# Eddy_Backplane.net
KiCad netlist of a schematic drawn in EAGLE
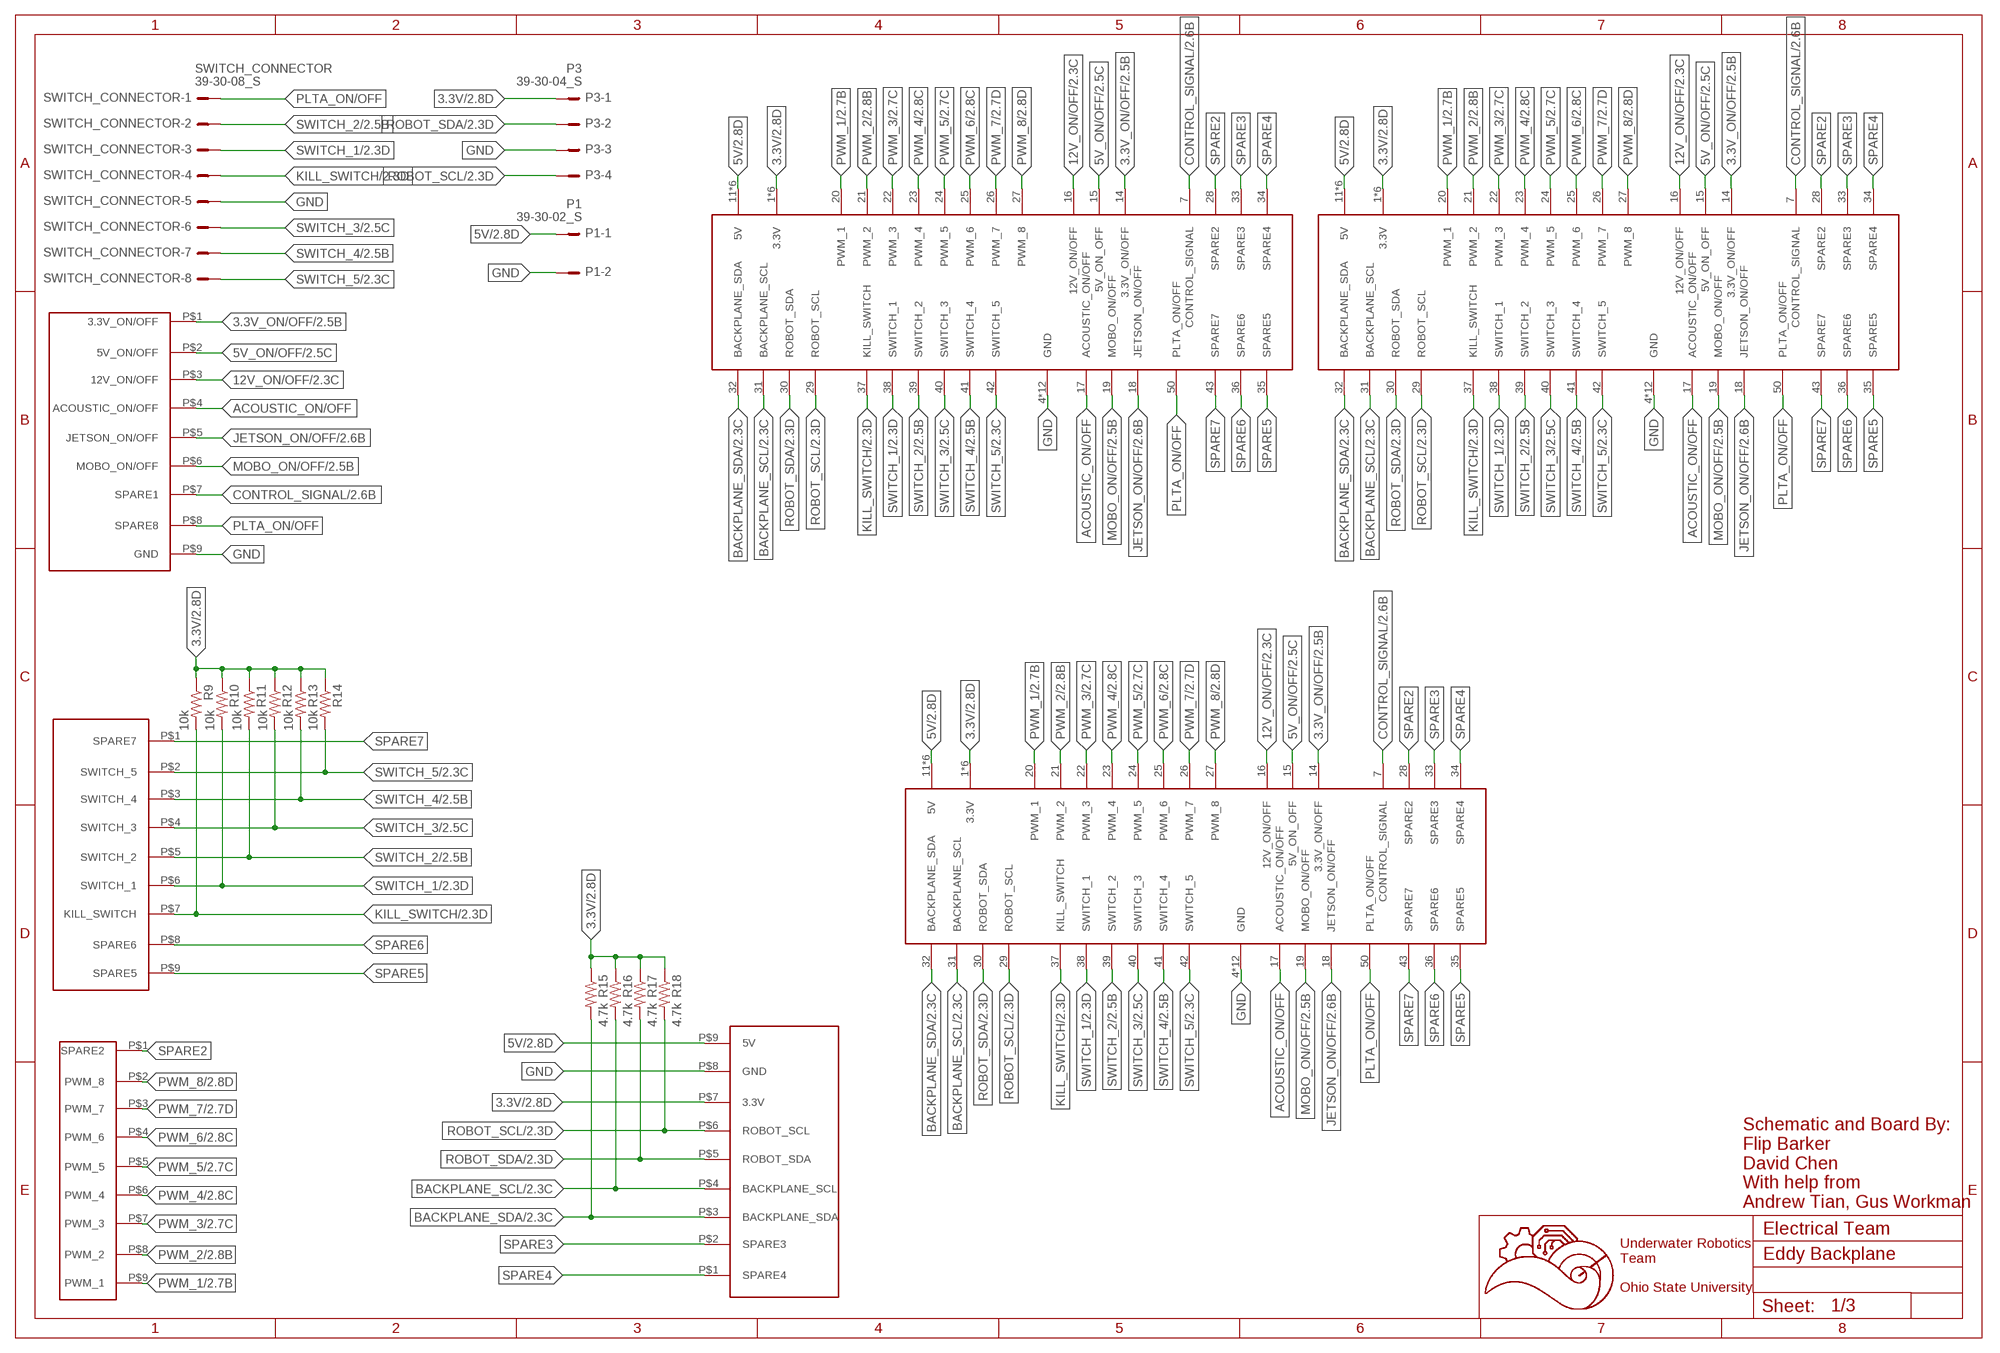
[diagram p0: schematic, sheet 1]
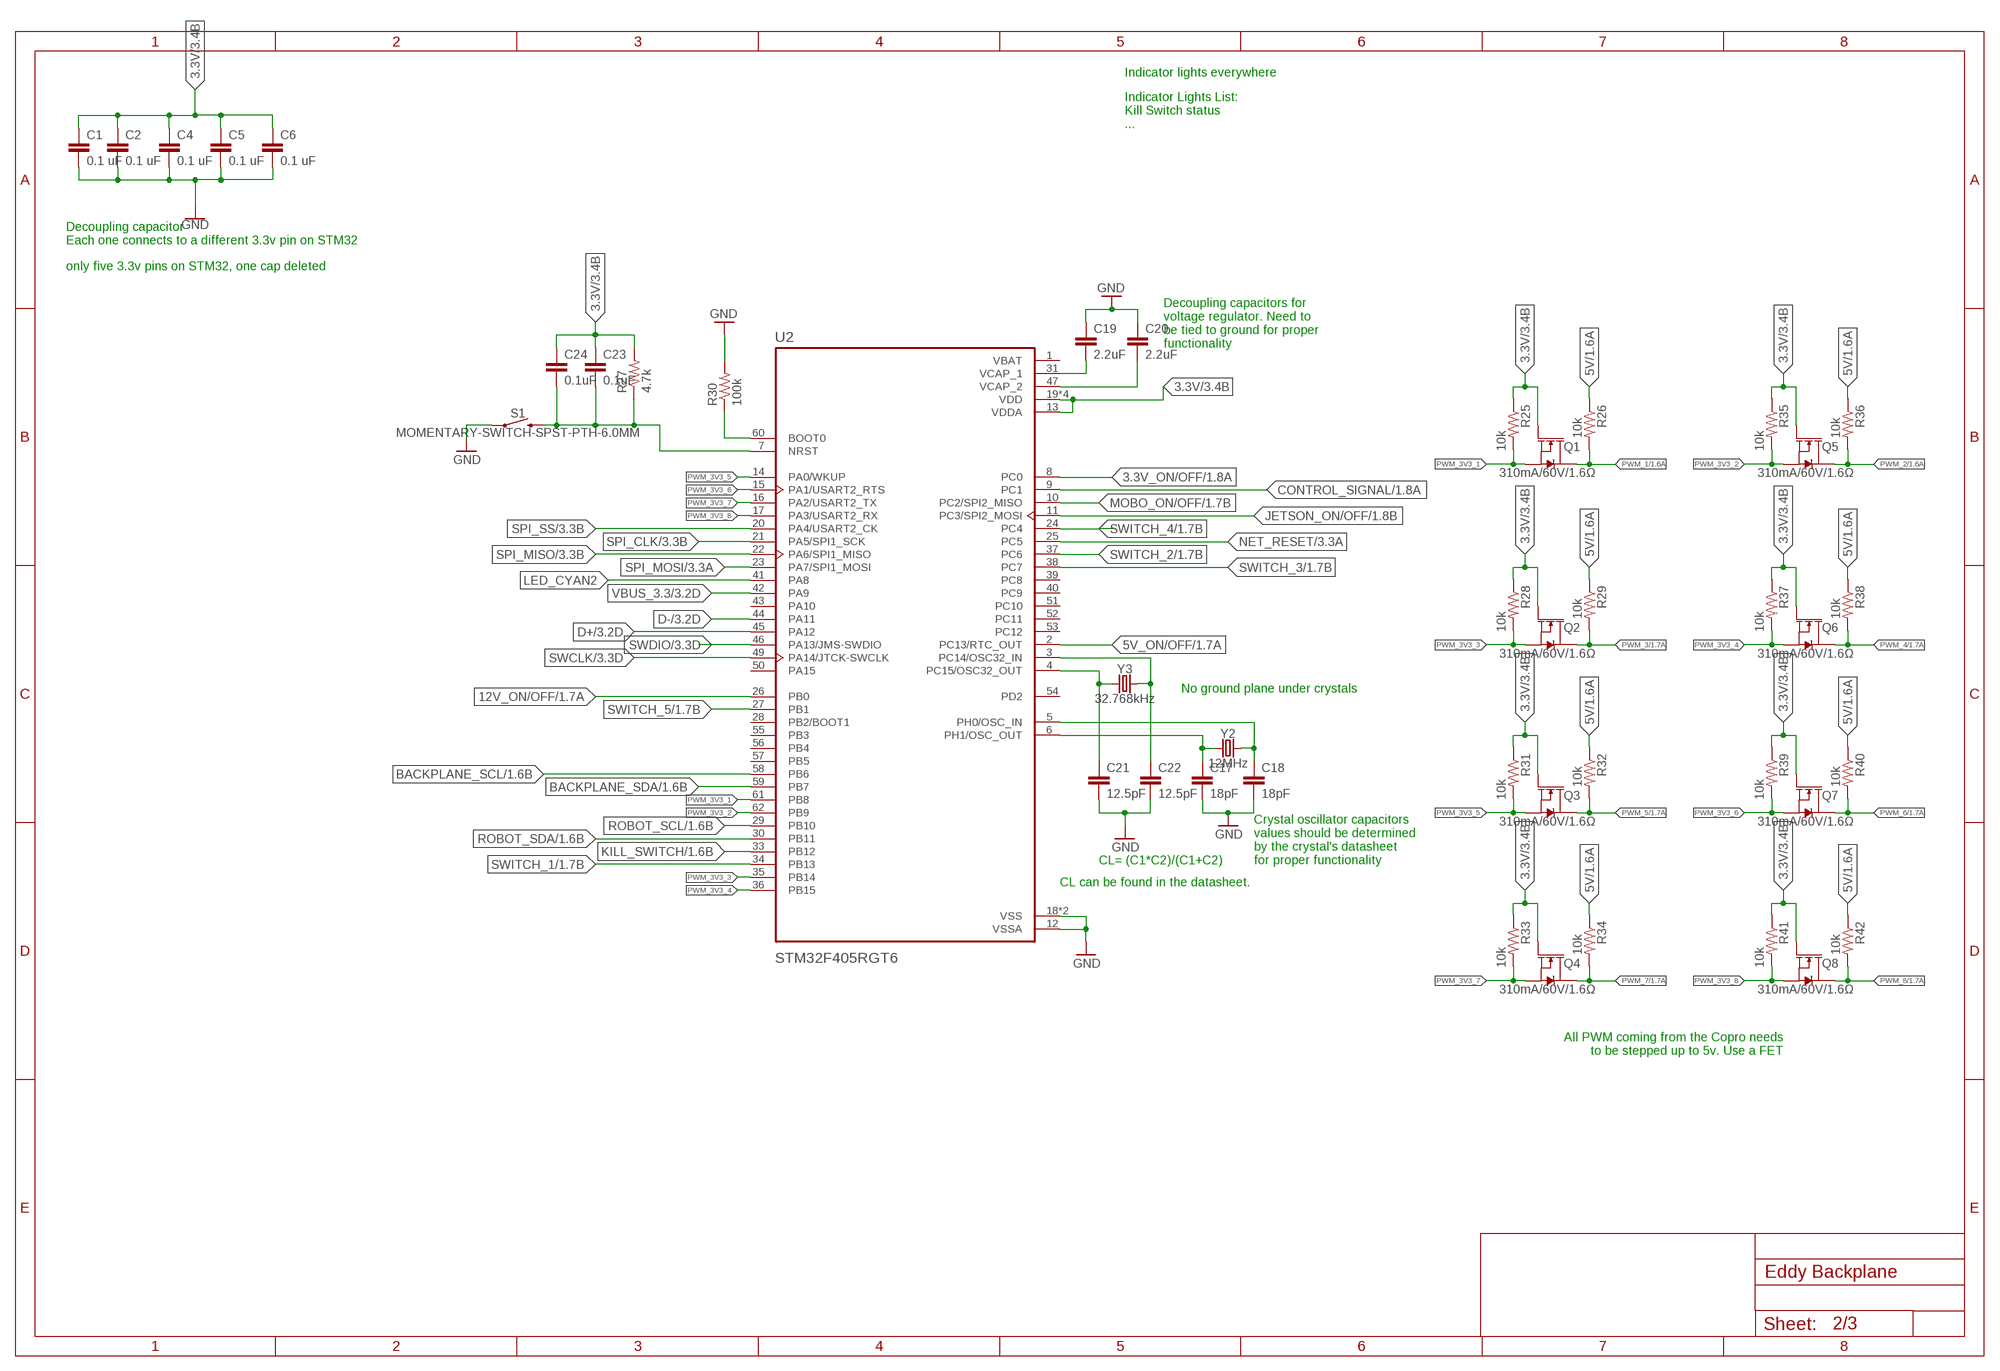
[diagram p1: schematic, sheet 2]
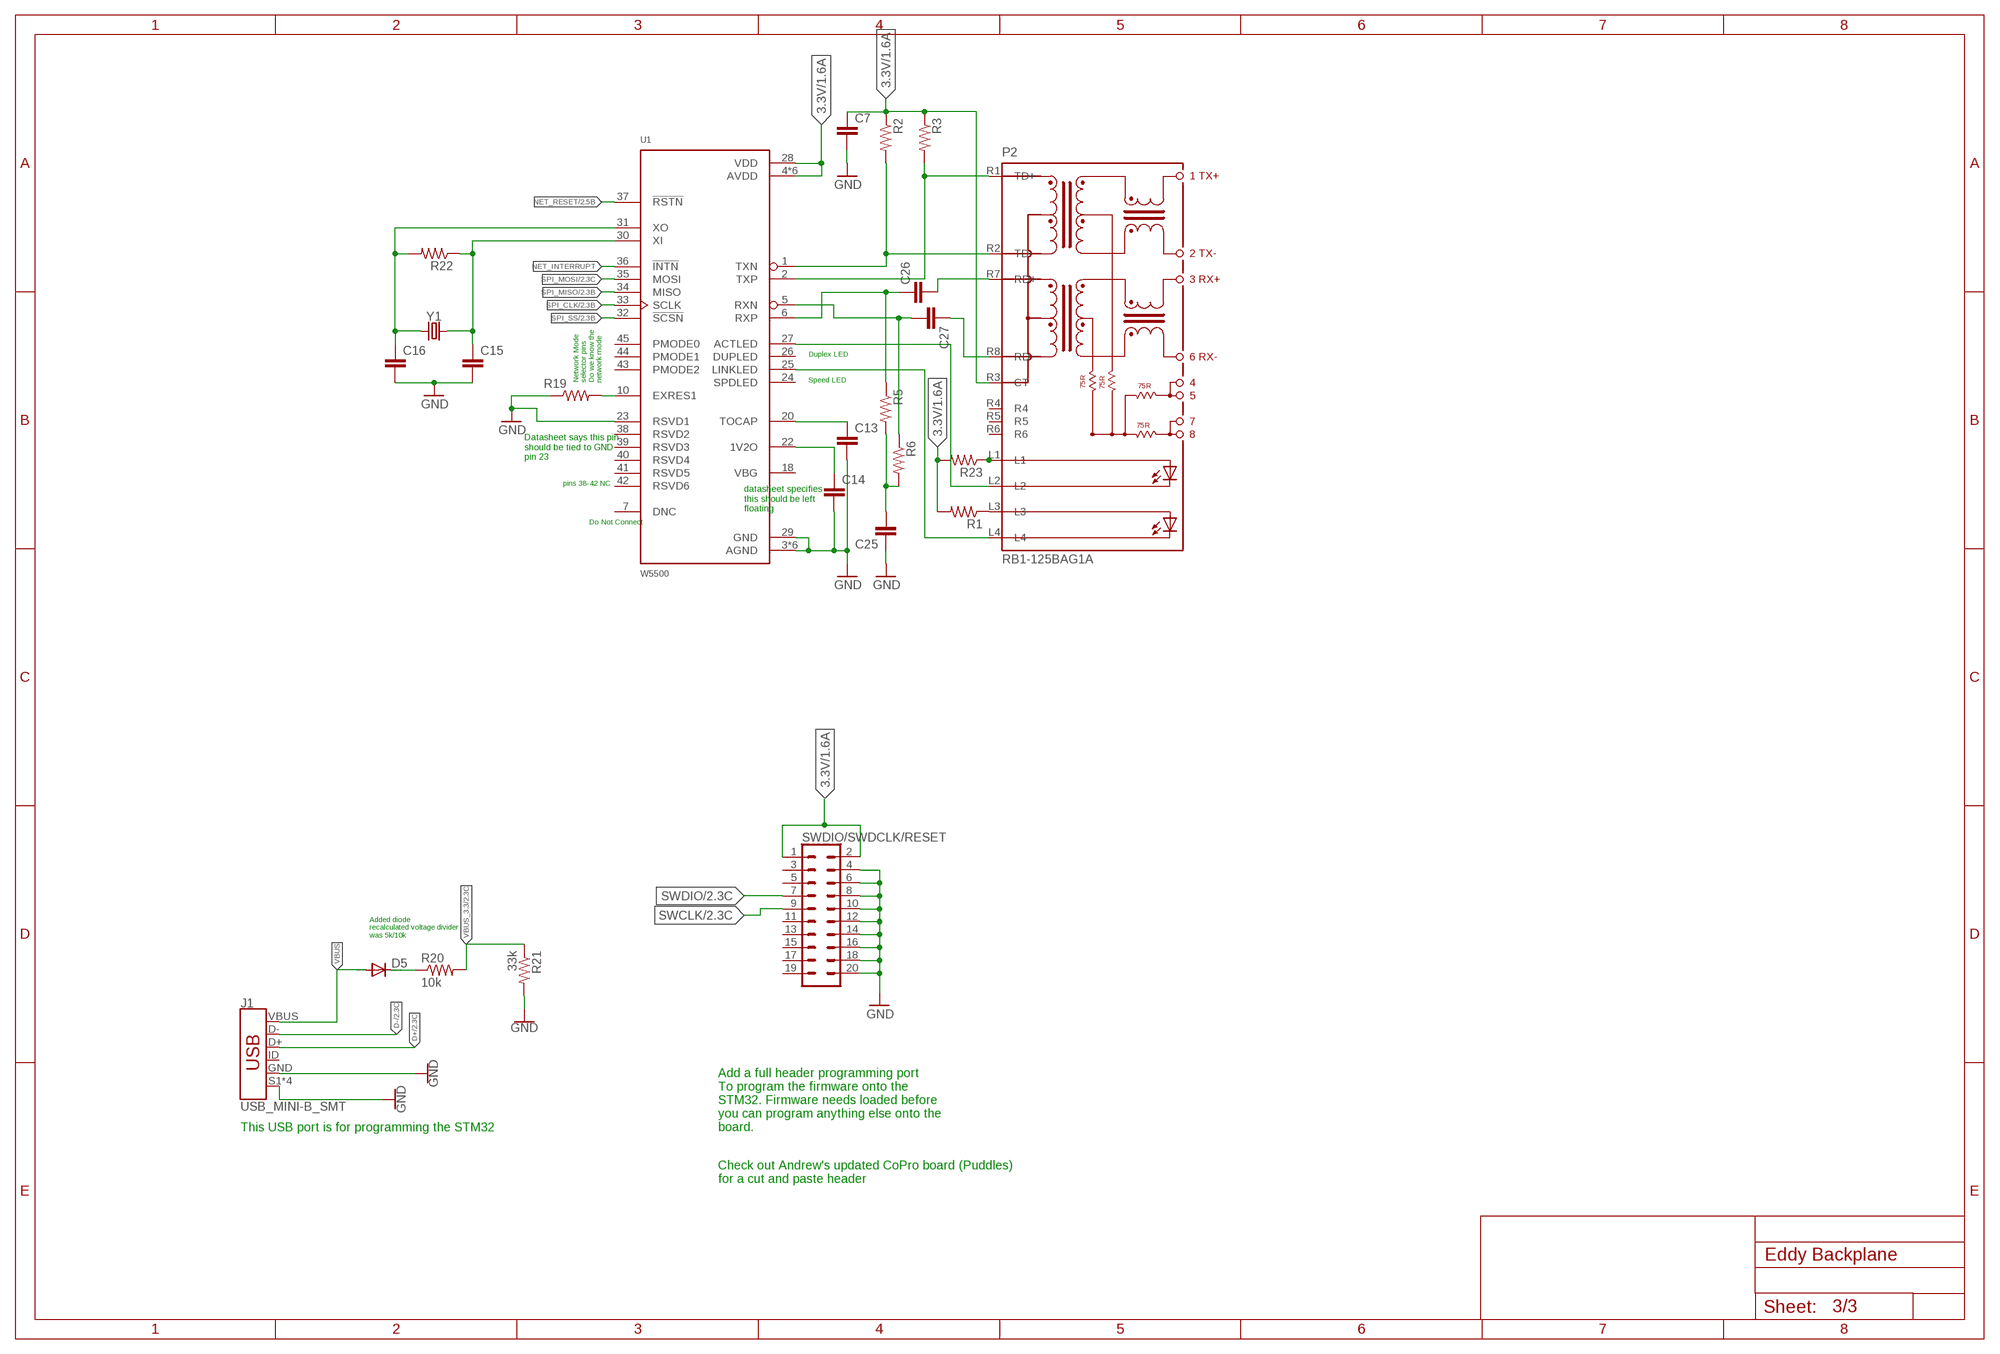
[diagram p2: schematic, sheet 3]

(export (version "E")
  (design (tool "Eeschema 10.0.6"))
  (components
    (comp (ref "C1")
      (value "0.1 uF")
      (footprint "eagle-import:C0603")
      (libsource (lib "eagle-import") (part "C-EUC0603"))
    )
    (comp (ref "C2")
      (value "0.1 uF")
      (footprint "eagle-import:C0603")
      (libsource (lib "eagle-import") (part "C-EUC0603"))
    )
    (comp (ref "C4")
      (value "0.1 uF")
      (footprint "eagle-import:C0603")
      (libsource (lib "eagle-import") (part "C-EUC0603"))
    )
    (comp (ref "C5")
      (value "0.1 uF")
      (footprint "eagle-import:C0603")
      (libsource (lib "eagle-import") (part "C-EUC0603"))
    )
    (comp (ref "C6")
      (value "0.1 uF")
      (footprint "eagle-import:C0603")
      (libsource (lib "eagle-import") (part "C-EUC0603"))
    )
    (comp (ref "C17")
      (value "18pF")
      (footprint "eagle-import:C0603")
      (libsource (lib "eagle-import") (part "C-EUC0603"))
    )
    (comp (ref "C18")
      (value "18pF")
      (footprint "eagle-import:C0603")
      (libsource (lib "eagle-import") (part "C-EUC0603"))
    )
    (comp (ref "C19")
      (value "2.2uF")
      (footprint "eagle-import:C0603")
      (libsource (lib "eagle-import") (part "C-EUC0603"))
    )
    (comp (ref "C20")
      (value "2.2uF")
      (footprint "eagle-import:C0603")
      (libsource (lib "eagle-import") (part "C-EUC0603"))
    )
    (comp (ref "C21")
      (value "12.5pF")
      (footprint "eagle-import:C0603")
      (libsource (lib "eagle-import") (part "C-EUC0603"))
    )
    (comp (ref "C22")
      (value "12.5pF")
      (footprint "eagle-import:C0603")
      (libsource (lib "eagle-import") (part "C-EUC0603"))
    )
    (comp (ref "C23")
      (value "0.1uF")
      (footprint "eagle-import:C0603")
      (libsource (lib "eagle-import") (part "C-EUC0603"))
    )
    (comp (ref "C24")
      (value "0.1uF")
      (footprint "eagle-import:C0603")
      (libsource (lib "eagle-import") (part "C-EUC0603"))
    )
    (comp (ref "Q1")
      (value "310mA/60V/1.6Ω")
      (footprint "eagle-import:SOT323")
      (libsource (lib "eagle-import") (part "MOSFET-NCH-2N7002PW"))
    )
    (comp (ref "Q2")
      (value "310mA/60V/1.6Ω")
      (footprint "eagle-import:SOT323")
      (libsource (lib "eagle-import") (part "MOSFET-NCH-2N7002PW"))
    )
    (comp (ref "Q3")
      (value "310mA/60V/1.6Ω")
      (footprint "eagle-import:SOT323")
      (libsource (lib "eagle-import") (part "MOSFET-NCH-2N7002PW"))
    )
    (comp (ref "Q4")
      (value "310mA/60V/1.6Ω")
      (footprint "eagle-import:SOT323")
      (libsource (lib "eagle-import") (part "MOSFET-NCH-2N7002PW"))
    )
    (comp (ref "Q5")
      (value "310mA/60V/1.6Ω")
      (footprint "eagle-import:SOT323")
      (libsource (lib "eagle-import") (part "MOSFET-NCH-2N7002PW"))
    )
    (comp (ref "Q6")
      (value "310mA/60V/1.6Ω")
      (footprint "eagle-import:SOT323")
      (libsource (lib "eagle-import") (part "MOSFET-NCH-2N7002PW"))
    )
    (comp (ref "Q7")
      (value "310mA/60V/1.6Ω")
      (footprint "eagle-import:SOT323")
      (libsource (lib "eagle-import") (part "MOSFET-NCH-2N7002PW"))
    )
    (comp (ref "Q8")
      (value "310mA/60V/1.6Ω")
      (footprint "eagle-import:SOT323")
      (libsource (lib "eagle-import") (part "MOSFET-NCH-2N7002PW"))
    )
    (comp (ref "R25")
      (value "10k")
      (footprint "eagle-import:R0603")
      (libsource (lib "eagle-import") (part "R-US_R0603"))
    )
    (comp (ref "R26")
      (value "10k")
      (footprint "eagle-import:R0603")
      (libsource (lib "eagle-import") (part "R-US_R0603"))
    )
    (comp (ref "R27")
      (value "4.7k")
      (footprint "eagle-import:R0603")
      (libsource (lib "eagle-import") (part "R-US_R0603"))
    )
    (comp (ref "R28")
      (value "10k")
      (footprint "eagle-import:R0603")
      (libsource (lib "eagle-import") (part "R-US_R0603"))
    )
    (comp (ref "R29")
      (value "10k")
      (footprint "eagle-import:R0603")
      (libsource (lib "eagle-import") (part "R-US_R0603"))
    )
    (comp (ref "R30")
      (value "100k")
      (footprint "eagle-import:R0603")
      (libsource (lib "eagle-import") (part "R-US_R0603"))
    )
    (comp (ref "R31")
      (value "10k")
      (footprint "eagle-import:R0603")
      (libsource (lib "eagle-import") (part "R-US_R0603"))
    )
    (comp (ref "R32")
      (value "10k")
      (footprint "eagle-import:R0603")
      (libsource (lib "eagle-import") (part "R-US_R0603"))
    )
    (comp (ref "R33")
      (value "10k")
      (footprint "eagle-import:R0603")
      (libsource (lib "eagle-import") (part "R-US_R0603"))
    )
    (comp (ref "R34")
      (value "10k")
      (footprint "eagle-import:R0603")
      (libsource (lib "eagle-import") (part "R-US_R0603"))
    )
    (comp (ref "R35")
      (value "10k")
      (footprint "eagle-import:R0603")
      (libsource (lib "eagle-import") (part "R-US_R0603"))
    )
    (comp (ref "R36")
      (value "10k")
      (footprint "eagle-import:R0603")
      (libsource (lib "eagle-import") (part "R-US_R0603"))
    )
    (comp (ref "R37")
      (value "10k")
      (footprint "eagle-import:R0603")
      (libsource (lib "eagle-import") (part "R-US_R0603"))
    )
    (comp (ref "R38")
      (value "10k")
      (footprint "eagle-import:R0603")
      (libsource (lib "eagle-import") (part "R-US_R0603"))
    )
    (comp (ref "R39")
      (value "10k")
      (footprint "eagle-import:R0603")
      (libsource (lib "eagle-import") (part "R-US_R0603"))
    )
    (comp (ref "R40")
      (value "10k")
      (footprint "eagle-import:R0603")
      (libsource (lib "eagle-import") (part "R-US_R0603"))
    )
    (comp (ref "R41")
      (value "10k")
      (footprint "eagle-import:R0603")
      (libsource (lib "eagle-import") (part "R-US_R0603"))
    )
    (comp (ref "R42")
      (value "10k")
      (footprint "eagle-import:R0603")
      (libsource (lib "eagle-import") (part "R-US_R0603"))
    )
    (comp (ref "S1")
      (value "MOMENTARY-SWITCH-SPST-PTH-6.0MM")
      (footprint "eagle-import:TACTILE_SWITCH_PTH_6.0MM")
      (libsource (lib "eagle-import") (part "MOMENTARY-SWITCH-SPST-PTH-6.0MM"))
    )
    (comp (ref "U2")
      (value "STM32F405RGT6")
      (footprint "eagle-import:QFP50P1200X1200X160-64N")
      (fields (field (name "MF") "STMicroelectronics"))
      (libsource (lib "eagle-import") (part "STM32F405RGT6"))
    )
    (comp (ref "Y2")
      (value "12MHz")
      (footprint "eagle-import:HC49US")
      (libsource (lib "eagle-import") (part "CRYSTAL-16MHZPTH-HC49US"))
    )
    (comp (ref "Y3")
      (value "32.768kHz")
      (footprint "eagle-import:CRYSTAL-SMD-3.2X1.5MM")
      (libsource (lib "eagle-import") (part "CRYSTAL-32.768KHZSMD-3.2X1.5"))
    )
    (comp (ref "P1")
      (value "39-30-02_S")
      (footprint "eagle-import:39-30-_02_")
      (libsource (lib "eagle-import") (part "39-30-?02?_S"))
    )
    (comp (ref "P3")
      (value "39-30-04_S")
      (footprint "eagle-import:39-30-_04_")
      (libsource (lib "eagle-import") (part "39-30-?04?_S"))
    )
    (comp (ref "PWR_ON")
      (value "929870-01-09_3")
      (footprint "eagle-import:929852-01-09_1ROW")
      (libsource (lib "eagle-import") (part "929870-01-09_3"))
    )
    (comp (ref "R9")
      (value "10k")
      (footprint "eagle-import:R0603")
      (libsource (lib "eagle-import") (part "R-US_R0603"))
    )
    (comp (ref "R10")
      (value "10k")
      (footprint "eagle-import:R0603")
      (libsource (lib "eagle-import") (part "R-US_R0603"))
    )
    (comp (ref "R11")
      (value "10k")
      (footprint "eagle-import:R0603")
      (libsource (lib "eagle-import") (part "R-US_R0603"))
    )
    (comp (ref "R12")
      (value "10k")
      (footprint "eagle-import:R0603")
      (libsource (lib "eagle-import") (part "R-US_R0603"))
    )
    (comp (ref "R13")
      (value "10k")
      (footprint "eagle-import:R0603")
      (libsource (lib "eagle-import") (part "R-US_R0603"))
    )
    (comp (ref "R14")
      (value "10k")
      (footprint "eagle-import:R0603")
      (libsource (lib "eagle-import") (part "R-US_R0603"))
    )
    (comp (ref "R15")
      (value "4.7k")
      (footprint "eagle-import:R0603")
      (libsource (lib "eagle-import") (part "R-US_R0603"))
    )
    (comp (ref "R16")
      (value "4.7k")
      (footprint "eagle-import:R0603")
      (libsource (lib "eagle-import") (part "R-US_R0603"))
    )
    (comp (ref "R17")
      (value "4.7k")
      (footprint "eagle-import:R0603")
      (libsource (lib "eagle-import") (part "R-US_R0603"))
    )
    (comp (ref "R18")
      (value "4.7k")
      (footprint "eagle-import:R0603")
      (libsource (lib "eagle-import") (part "R-US_R0603"))
    )
    (comp (ref "SWITCH_CONN")
      (value "929870-01-09_1")
      (footprint "eagle-import:929852-01-09_1ROW")
      (libsource (lib "eagle-import") (part "929870-01-09_1"))
    )
    (comp (ref "SWITCH_CONNECTOR")
      (value "39-30-08_S")
      (footprint "eagle-import:39-30-_08_")
      (libsource (lib "eagle-import") (part "39-30-?08?_S"))
    )
    (comp (ref "U$1")
      (value "5530843-FEMALE")
      (footprint "eagle-import:5530843-6-BACKPLANEMATE")
      (libsource (lib "eagle-import") (part "5530843-FEMALE"))
    )
    (comp (ref "U$2")
      (value "5530843-FEMALE")
      (footprint "eagle-import:5530843-6-BACKPLANEMATE")
      (libsource (lib "eagle-import") (part "5530843-FEMALE"))
    )
    (comp (ref "U$3")
      (value "5530843-FEMALE")
      (footprint "eagle-import:5530843-6-BACKPLANEMATE")
      (libsource (lib "eagle-import") (part "5530843-FEMALE"))
    )
    (comp (ref "U$6")
      (value "929870-01-09_2")
      (footprint "eagle-import:929852-01-09_1ROW")
      (libsource (lib "eagle-import") (part "929870-01-09_2"))
    )
    (comp (ref "U$8")
      (value "929870-01-09_4")
      (footprint "eagle-import:929852-01-09_1ROW")
      (libsource (lib "eagle-import") (part "929870-01-09_4"))
    )
    (comp (ref "C7")
      (value "C-EUC0603")
      (footprint "eagle-import:C0603")
      (libsource (lib "eagle-import") (part "C-EUC0603"))
    )
    (comp (ref "C13")
      (value "C-EUC0603")
      (footprint "eagle-import:C0603")
      (libsource (lib "eagle-import") (part "C-EUC0603"))
    )
    (comp (ref "C14")
      (value "C-EUC0603")
      (footprint "eagle-import:C0603")
      (libsource (lib "eagle-import") (part "C-EUC0603"))
    )
    (comp (ref "C15")
      (value "C-EUC0603")
      (footprint "eagle-import:C0603")
      (libsource (lib "eagle-import") (part "C-EUC0603"))
    )
    (comp (ref "C16")
      (value "C-EUC0603")
      (footprint "eagle-import:C0603")
      (libsource (lib "eagle-import") (part "C-EUC0603"))
    )
    (comp (ref "C25")
      (value "C-EUC0603")
      (footprint "eagle-import:C0603")
      (libsource (lib "eagle-import") (part "C-EUC0603"))
    )
    (comp (ref "C26")
      (value "C-EUC0603")
      (footprint "eagle-import:C0603")
      (libsource (lib "eagle-import") (part "C-EUC0603"))
    )
    (comp (ref "C27")
      (value "C-EUC0603")
      (footprint "eagle-import:C0603")
      (libsource (lib "eagle-import") (part "C-EUC0603"))
    )
    (comp (ref "D5")
      (value "DIODE-SMB")
      (footprint "eagle-import:SMB")
      (libsource (lib "eagle-import") (part "DIODE-SMB"))
    )
    (comp (ref "J1")
      (value "USB_MINI-B_SMT")
      (footprint "eagle-import:USB-MINIB")
      (libsource (lib "eagle-import") (part "USB_MINI-B_SMT"))
    )
    (comp (ref "P2")
      (value "RB1-125BAG1A")
      (footprint "eagle-import:WIZNET_RB1-125BAG1A")
      (fields (field (name "MF") "WIZnet"))
      (libsource (lib "eagle-import") (part "RB1-125BAG1A"))
    )
    (comp (ref "R1")
      (value "R-US_R0603")
      (footprint "eagle-import:R0603")
      (libsource (lib "eagle-import") (part "R-US_R0603"))
    )
    (comp (ref "R2")
      (value "R-US_R0603")
      (footprint "eagle-import:R0603")
      (libsource (lib "eagle-import") (part "R-US_R0603"))
    )
    (comp (ref "R3")
      (value "R-US_R0603")
      (footprint "eagle-import:R0603")
      (libsource (lib "eagle-import") (part "R-US_R0603"))
    )
    (comp (ref "R5")
      (value "R-US_R0603")
      (footprint "eagle-import:R0603")
      (libsource (lib "eagle-import") (part "R-US_R0603"))
    )
    (comp (ref "R6")
      (value "R-US_R0603")
      (footprint "eagle-import:R0603")
      (libsource (lib "eagle-import") (part "R-US_R0603"))
    )
    (comp (ref "R19")
      (value "R-US_R0603")
      (footprint "eagle-import:R0603")
      (libsource (lib "eagle-import") (part "R-US_R0603"))
    )
    (comp (ref "R20")
      (value "10k")
      (footprint "eagle-import:R0603")
      (libsource (lib "eagle-import") (part "R-US_R0603"))
    )
    (comp (ref "R21")
      (value "33k")
      (footprint "eagle-import:R0603")
      (libsource (lib "eagle-import") (part "R-US_R0603"))
    )
    (comp (ref "R22")
      (value "R-US_R0603")
      (footprint "eagle-import:R0603")
      (libsource (lib "eagle-import") (part "R-US_R0603"))
    )
    (comp (ref "R23")
      (value "R-US_R0603")
      (footprint "eagle-import:R0603")
      (libsource (lib "eagle-import") (part "R-US_R0603"))
    )
    (comp (ref "SWDIO/SWDCLK/RESET")
      (value "CONN_10X2")
      (footprint "eagle-import:2X10")
      (libsource (lib "eagle-import") (part "CONN_10X2"))
    )
    (comp (ref "U1")
      (value "W5500")
      (footprint "eagle-import:QFP50P900X900X160-48N")
      (fields (field (name "MF") "WIZnet"))
      (libsource (lib "eagle-import") (part "W5500"))
    )
    (comp (ref "Y1")
      (value "CRYSTALPTH-HC49US")
      (footprint "eagle-import:HC49US")
      (libsource (lib "eagle-import") (part "CRYSTALPTH-HC49US"))
    )
  )
  (nets
    (net (code "1") (name "3.3V") (class "Default")
      (node (ref "C1") (pin "1") (pinfunction "1_1") (pintype "passive"))
      (node (ref "C2") (pin "1") (pinfunction "1_1") (pintype "passive"))
      (node (ref "C23") (pin "1") (pinfunction "1_1") (pintype "passive"))
      (node (ref "C24") (pin "1") (pinfunction "1_1") (pintype "passive"))
      (node (ref "C4") (pin "1") (pinfunction "1_1") (pintype "passive"))
      (node (ref "C5") (pin "1") (pinfunction "1_1") (pintype "passive"))
      (node (ref "C6") (pin "1") (pinfunction "1_1") (pintype "passive"))
      (node (ref "C7") (pin "1") (pinfunction "1_1") (pintype "passive"))
      (node (ref "P2") (pin "R3") (pinfunction "CT_R3") (pintype "input"))
      (node (ref "P3") (pin "1") (pinfunction "P_1") (pintype "passive"))
      (node (ref "Q1") (pin "1") (pinfunction "G_1") (pintype "bidirectional"))
      (node (ref "Q2") (pin "1") (pinfunction "G_1") (pintype "bidirectional"))
      (node (ref "Q3") (pin "1") (pinfunction "G_1") (pintype "bidirectional"))
      (node (ref "Q4") (pin "1") (pinfunction "G_1") (pintype "bidirectional"))
      (node (ref "Q5") (pin "1") (pinfunction "G_1") (pintype "bidirectional"))
      (node (ref "Q6") (pin "1") (pinfunction "G_1") (pintype "bidirectional"))
      (node (ref "Q7") (pin "1") (pinfunction "G_1") (pintype "bidirectional"))
      (node (ref "Q8") (pin "1") (pinfunction "G_1") (pintype "bidirectional"))
      (node (ref "R1") (pin "2") (pinfunction "2_2") (pintype "passive"))
      (node (ref "R10") (pin "1") (pinfunction "1_1") (pintype "passive"))
      (node (ref "R11") (pin "1") (pinfunction "1_1") (pintype "passive"))
      (node (ref "R12") (pin "1") (pinfunction "1_1") (pintype "passive"))
      (node (ref "R13") (pin "1") (pinfunction "1_1") (pintype "passive"))
      (node (ref "R14") (pin "1") (pinfunction "1_1") (pintype "passive"))
      (node (ref "R15") (pin "1") (pinfunction "1_1") (pintype "passive"))
      (node (ref "R16") (pin "1") (pinfunction "1_1") (pintype "passive"))
      (node (ref "R17") (pin "1") (pinfunction "1_1") (pintype "passive"))
      (node (ref "R18") (pin "1") (pinfunction "1_1") (pintype "passive"))
      (node (ref "R2") (pin "1") (pinfunction "1_1") (pintype "passive"))
      (node (ref "R23") (pin "2") (pinfunction "2_2") (pintype "passive"))
      (node (ref "R25") (pin "1") (pinfunction "1_1") (pintype "passive"))
      (node (ref "R27") (pin "2") (pinfunction "2_2") (pintype "passive"))
      (node (ref "R28") (pin "1") (pinfunction "1_1") (pintype "passive"))
      (node (ref "R3") (pin "1") (pinfunction "1_1") (pintype "passive"))
      (node (ref "R31") (pin "1") (pinfunction "1_1") (pintype "passive"))
      (node (ref "R33") (pin "1") (pinfunction "1_1") (pintype "passive"))
      (node (ref "R35") (pin "1") (pinfunction "1_1") (pintype "passive"))
      (node (ref "R37") (pin "1") (pinfunction "1_1") (pintype "passive"))
      (node (ref "R39") (pin "1") (pinfunction "1_1") (pintype "passive"))
      (node (ref "R41") (pin "1") (pinfunction "1_1") (pintype "passive"))
      (node (ref "R9") (pin "1") (pinfunction "1_1") (pintype "passive"))
      (node (ref "SWDIO/SWDCLK/RESET") (pin "1") (pinfunction "1_1") (pintype "passive"))
      (node (ref "SWDIO/SWDCLK/RESET") (pin "2") (pinfunction "2_2") (pintype "passive"))
      (node (ref "U$1") (pin "1") (pinfunction "3.3V_1") (pintype "bidirectional"))
      (node (ref "U$1") (pin "2") (pinfunction "3.3V_2") (pintype "bidirectional"))
      (node (ref "U$1") (pin "3") (pinfunction "3.3V_3") (pintype "bidirectional"))
      (node (ref "U$1") (pin "54") (pinfunction "3.3V_54") (pintype "bidirectional"))
      (node (ref "U$1") (pin "55") (pinfunction "3.3V_55") (pintype "bidirectional"))
      (node (ref "U$1") (pin "56") (pinfunction "3.3V_56") (pintype "bidirectional"))
      (node (ref "U$2") (pin "1") (pinfunction "3.3V_1") (pintype "bidirectional"))
      (node (ref "U$2") (pin "2") (pinfunction "3.3V_2") (pintype "bidirectional"))
      (node (ref "U$2") (pin "3") (pinfunction "3.3V_3") (pintype "bidirectional"))
      (node (ref "U$2") (pin "54") (pinfunction "3.3V_54") (pintype "bidirectional"))
      (node (ref "U$2") (pin "55") (pinfunction "3.3V_55") (pintype "bidirectional"))
      (node (ref "U$2") (pin "56") (pinfunction "3.3V_56") (pintype "bidirectional"))
      (node (ref "U$3") (pin "1") (pinfunction "3.3V_1") (pintype "bidirectional"))
      (node (ref "U$3") (pin "2") (pinfunction "3.3V_2") (pintype "bidirectional"))
      (node (ref "U$3") (pin "3") (pinfunction "3.3V_3") (pintype "bidirectional"))
      (node (ref "U$3") (pin "54") (pinfunction "3.3V_54") (pintype "bidirectional"))
      (node (ref "U$3") (pin "55") (pinfunction "3.3V_55") (pintype "bidirectional"))
      (node (ref "U$3") (pin "56") (pinfunction "3.3V_56") (pintype "bidirectional"))
      (node (ref "U$8") (pin "P$7") (pinfunction "3.3V_P$7") (pintype "bidirectional"))
      (node (ref "U1") (pin "11") (pinfunction "AVDD_11") (pintype "power_in"))
      (node (ref "U1") (pin "15") (pinfunction "AVDD_15") (pintype "power_in"))
      (node (ref "U1") (pin "17") (pinfunction "AVDD_17") (pintype "power_in"))
      (node (ref "U1") (pin "21") (pinfunction "AVDD_21") (pintype "power_in"))
      (node (ref "U1") (pin "28") (pinfunction "VDD_28") (pintype "power_in"))
      (node (ref "U1") (pin "4") (pinfunction "AVDD_4") (pintype "power_in"))
      (node (ref "U1") (pin "8") (pinfunction "AVDD_8") (pintype "power_in"))
      (node (ref "U2") (pin "13") (pinfunction "VDDA_13") (pintype "power_in"))
      (node (ref "U2") (pin "19") (pinfunction "VDD_19") (pintype "power_in"))
      (node (ref "U2") (pin "32") (pinfunction "VDD_32") (pintype "power_in"))
      (node (ref "U2") (pin "48") (pinfunction "VDD_48") (pintype "power_in"))
      (node (ref "U2") (pin "64") (pinfunction "VDD_64") (pintype "power_in"))
    )
    (net (code "2") (name "3.3V_ON{slash}OFF") (class "Default")
      (node (ref "PWR_ON") (pin "P$1") (pinfunction "3.3V_ON/OFF_P$1") (pintype "bidirectional"))
      (node (ref "U$1") (pin "14") (pinfunction "3.3V_ON/OFF_14") (pintype "bidirectional"))
      (node (ref "U$2") (pin "14") (pinfunction "3.3V_ON/OFF_14") (pintype "bidirectional"))
      (node (ref "U$3") (pin "14") (pinfunction "3.3V_ON/OFF_14") (pintype "bidirectional"))
      (node (ref "U2") (pin "8") (pinfunction "PC0_8") (pintype "bidirectional"))
    )
    (net (code "3") (name "5V") (class "Default")
      (node (ref "P1") (pin "1") (pinfunction "P_1") (pintype "passive"))
      (node (ref "R26") (pin "1") (pinfunction "1_1") (pintype "passive"))
      (node (ref "R29") (pin "1") (pinfunction "1_1") (pintype "passive"))
      (node (ref "R32") (pin "1") (pinfunction "1_1") (pintype "passive"))
      (node (ref "R34") (pin "1") (pinfunction "1_1") (pintype "passive"))
      (node (ref "R36") (pin "1") (pinfunction "1_1") (pintype "passive"))
      (node (ref "R38") (pin "1") (pinfunction "1_1") (pintype "passive"))
      (node (ref "R40") (pin "1") (pinfunction "1_1") (pintype "passive"))
      (node (ref "R42") (pin "1") (pinfunction "1_1") (pintype "passive"))
      (node (ref "U$1") (pin "11") (pinfunction "5V_11") (pintype "bidirectional"))
      (node (ref "U$1") (pin "12") (pinfunction "5V_12") (pintype "bidirectional"))
      (node (ref "U$1") (pin "13") (pinfunction "5V_13") (pintype "bidirectional"))
      (node (ref "U$1") (pin "44") (pinfunction "5V_44") (pintype "bidirectional"))
      (node (ref "U$1") (pin "45") (pinfunction "5V_45") (pintype "bidirectional"))
      (node (ref "U$1") (pin "46") (pinfunction "5V_46") (pintype "bidirectional"))
      (node (ref "U$2") (pin "11") (pinfunction "5V_11") (pintype "bidirectional"))
      (node (ref "U$2") (pin "12") (pinfunction "5V_12") (pintype "bidirectional"))
      (node (ref "U$2") (pin "13") (pinfunction "5V_13") (pintype "bidirectional"))
      (node (ref "U$2") (pin "44") (pinfunction "5V_44") (pintype "bidirectional"))
      (node (ref "U$2") (pin "45") (pinfunction "5V_45") (pintype "bidirectional"))
      (node (ref "U$2") (pin "46") (pinfunction "5V_46") (pintype "bidirectional"))
      (node (ref "U$3") (pin "11") (pinfunction "5V_11") (pintype "bidirectional"))
      (node (ref "U$3") (pin "12") (pinfunction "5V_12") (pintype "bidirectional"))
      (node (ref "U$3") (pin "13") (pinfunction "5V_13") (pintype "bidirectional"))
      (node (ref "U$3") (pin "44") (pinfunction "5V_44") (pintype "bidirectional"))
      (node (ref "U$3") (pin "45") (pinfunction "5V_45") (pintype "bidirectional"))
      (node (ref "U$3") (pin "46") (pinfunction "5V_46") (pintype "bidirectional"))
      (node (ref "U$8") (pin "P$9") (pinfunction "5V_P$9") (pintype "bidirectional"))
    )
    (net (code "4") (name "5V_ON{slash}OFF") (class "Default")
      (node (ref "PWR_ON") (pin "P$2") (pinfunction "5V_ON/OFF_P$2") (pintype "bidirectional"))
      (node (ref "U$1") (pin "15") (pinfunction "5V_ON_OFF_15") (pintype "bidirectional"))
      (node (ref "U$2") (pin "15") (pinfunction "5V_ON_OFF_15") (pintype "bidirectional"))
      (node (ref "U$3") (pin "15") (pinfunction "5V_ON_OFF_15") (pintype "bidirectional"))
      (node (ref "U2") (pin "2") (pinfunction "PC13/RTC_OUT_2") (pintype "bidirectional"))
    )
    (net (code "5") (name "12V_ON{slash}OFF") (class "Default")
      (node (ref "PWR_ON") (pin "P$3") (pinfunction "12V_ON/OFF_P$3") (pintype "bidirectional"))
      (node (ref "U$1") (pin "16") (pinfunction "12V_ON/OFF_16") (pintype "bidirectional"))
      (node (ref "U$2") (pin "16") (pinfunction "12V_ON/OFF_16") (pintype "bidirectional"))
      (node (ref "U$3") (pin "16") (pinfunction "12V_ON/OFF_16") (pintype "bidirectional"))
      (node (ref "U2") (pin "26") (pinfunction "PB0_26") (pintype "bidirectional"))
    )
    (net (code "6") (name "ACOUSTIC_ON{slash}OFF") (class "Default")
      (node (ref "PWR_ON") (pin "P$4") (pinfunction "ACOUSTIC_ON/OFF_P$4") (pintype "bidirectional"))
      (node (ref "U$1") (pin "17") (pinfunction "ACOUSTIC_ON/OFF_17") (pintype "bidirectional"))
      (node (ref "U$2") (pin "17") (pinfunction "ACOUSTIC_ON/OFF_17") (pintype "bidirectional"))
      (node (ref "U$3") (pin "17") (pinfunction "ACOUSTIC_ON/OFF_17") (pintype "bidirectional"))
    )
    (net (code "7") (name "BACKPLANE_SCL") (class "Default")
      (node (ref "R16") (pin "2") (pinfunction "2_2") (pintype "passive"))
      (node (ref "U$1") (pin "31") (pinfunction "BACKPLANE_SCL_31") (pintype "bidirectional"))
      (node (ref "U$2") (pin "31") (pinfunction "BACKPLANE_SCL_31") (pintype "bidirectional"))
      (node (ref "U$3") (pin "31") (pinfunction "BACKPLANE_SCL_31") (pintype "bidirectional"))
      (node (ref "U$8") (pin "P$4") (pinfunction "BACKPLANE_SCL_P$4") (pintype "bidirectional"))
      (node (ref "U2") (pin "58") (pinfunction "PB6_58") (pintype "bidirectional"))
    )
    (net (code "8") (name "BACKPLANE_SDA") (class "Default")
      (node (ref "R15") (pin "2") (pinfunction "2_2") (pintype "passive"))
      (node (ref "U$1") (pin "32") (pinfunction "BACKPLANE_SDA_32") (pintype "bidirectional"))
      (node (ref "U$2") (pin "32") (pinfunction "BACKPLANE_SDA_32") (pintype "bidirectional"))
      (node (ref "U$3") (pin "32") (pinfunction "BACKPLANE_SDA_32") (pintype "bidirectional"))
      (node (ref "U$8") (pin "P$3") (pinfunction "BACKPLANE_SDA_P$3") (pintype "bidirectional"))
      (node (ref "U2") (pin "59") (pinfunction "PB7_59") (pintype "bidirectional"))
    )
    (net (code "9") (name "CONTROL_SIGNAL") (class "Default")
      (node (ref "PWR_ON") (pin "P$7") (pinfunction "SPARE1_P$7") (pintype "bidirectional"))
      (node (ref "U$1") (pin "7") (pinfunction "CONTROL_SIGNAL_7") (pintype "bidirectional"))
      (node (ref "U$2") (pin "7") (pinfunction "CONTROL_SIGNAL_7") (pintype "bidirectional"))
      (node (ref "U$3") (pin "7") (pinfunction "CONTROL_SIGNAL_7") (pintype "bidirectional"))
      (node (ref "U2") (pin "9") (pinfunction "PC1_9") (pintype "bidirectional"))
    )
    (net (code "10") (name "D+") (class "Default")
      (node (ref "J1") (pin "D+") (pinfunction "D+_D+") (pintype "bidirectional"))
      (node (ref "U2") (pin "45") (pinfunction "PA12_45") (pintype "bidirectional"))
    )
    (net (code "11") (name "D-") (class "Default")
      (node (ref "J1") (pin "D-") (pinfunction "D-_D-") (pintype "bidirectional"))
      (node (ref "U2") (pin "44") (pinfunction "PA11_44") (pintype "bidirectional"))
    )
    (net (code "12") (name "GND") (class "Default")
      (node (ref "C1") (pin "2") (pinfunction "2_2") (pintype "passive"))
      (node (ref "C13") (pin "2") (pinfunction "2_2") (pintype "passive"))
      (node (ref "C14") (pin "2") (pinfunction "2_2") (pintype "passive"))
      (node (ref "C15") (pin "2") (pinfunction "2_2") (pintype "passive"))
      (node (ref "C16") (pin "2") (pinfunction "2_2") (pintype "passive"))
      (node (ref "C17") (pin "2") (pinfunction "2_2") (pintype "passive"))
      (node (ref "C18") (pin "2") (pinfunction "2_2") (pintype "passive"))
      (node (ref "C19") (pin "1") (pinfunction "1_1") (pintype "passive"))
      (node (ref "C2") (pin "2") (pinfunction "2_2") (pintype "passive"))
      (node (ref "C20") (pin "1") (pinfunction "1_1") (pintype "passive"))
      (node (ref "C21") (pin "2") (pinfunction "2_2") (pintype "passive"))
      (node (ref "C22") (pin "2") (pinfunction "2_2") (pintype "passive"))
      (node (ref "C25") (pin "1") (pinfunction "1_1") (pintype "passive"))
      (node (ref "C4") (pin "2") (pinfunction "2_2") (pintype "passive"))
      (node (ref "C5") (pin "2") (pinfunction "2_2") (pintype "passive"))
      (node (ref "C6") (pin "2") (pinfunction "2_2") (pintype "passive"))
      (node (ref "C7") (pin "2") (pinfunction "2_2") (pintype "passive"))
      (node (ref "J1") (pin "GND") (pinfunction "GND_GND") (pintype "power_in"))
      (node (ref "J1") (pin "S1") (pinfunction "SHIELD_S1") (pintype "bidirectional"))
      (node (ref "J1") (pin "S2") (pinfunction "SHIELD_S2") (pintype "bidirectional"))
      (node (ref "J1") (pin "S3") (pinfunction "SHIELD_S3") (pintype "bidirectional"))
      (node (ref "J1") (pin "S4") (pinfunction "SHIELD_S4") (pintype "bidirectional"))
      (node (ref "P1") (pin "2") (pinfunction "P_2") (pintype "passive"))
      (node (ref "P3") (pin "3") (pinfunction "P_3") (pintype "passive"))
      (node (ref "PWR_ON") (pin "P$9") (pinfunction "GND_P$9") (pintype "bidirectional"))
      (node (ref "R19") (pin "1") (pinfunction "1_1") (pintype "passive"))
      (node (ref "R21") (pin "2") (pinfunction "2_2") (pintype "passive"))
      (node (ref "R30") (pin "2") (pinfunction "2_2") (pintype "passive"))
      (node (ref "S1") (pin "1") (pinfunction "1_1") (pintype "passive"))
      (node (ref "SWDIO/SWDCLK/RESET") (pin "10") (pinfunction "10_10") (pintype "passive"))
      (node (ref "SWDIO/SWDCLK/RESET") (pin "12") (pinfunction "12_12") (pintype "passive"))
      (node (ref "SWDIO/SWDCLK/RESET") (pin "14") (pinfunction "14_14") (pintype "passive"))
      (node (ref "SWDIO/SWDCLK/RESET") (pin "16") (pinfunction "16_16") (pintype "passive"))
      (node (ref "SWDIO/SWDCLK/RESET") (pin "18") (pinfunction "18_18") (pintype "passive"))
      (node (ref "SWDIO/SWDCLK/RESET") (pin "20") (pinfunction "20_20") (pintype "passive"))
      (node (ref "SWDIO/SWDCLK/RESET") (pin "4") (pinfunction "4_4") (pintype "passive"))
      (node (ref "SWDIO/SWDCLK/RESET") (pin "6") (pinfunction "6_6") (pintype "passive"))
      (node (ref "SWDIO/SWDCLK/RESET") (pin "8") (pinfunction "8_8") (pintype "passive"))
      (node (ref "SWITCH_CONNECTOR") (pin "5") (pinfunction "P_5") (pintype "passive"))
      (node (ref "U$1") (pin "10") (pinfunction "GND_10") (pintype "bidirectional"))
      (node (ref "U$1") (pin "4") (pinfunction "GND_4") (pintype "bidirectional"))
      (node (ref "U$1") (pin "47") (pinfunction "GND_47") (pintype "bidirectional"))
      (node (ref "U$1") (pin "48") (pinfunction "GND_48") (pintype "bidirectional"))
      (node (ref "U$1") (pin "49") (pinfunction "GND_49") (pintype "bidirectional"))
      (node (ref "U$1") (pin "5") (pinfunction "GND_5") (pintype "bidirectional"))
      (node (ref "U$1") (pin "51") (pinfunction "GND_51") (pintype "bidirectional"))
      (node (ref "U$1") (pin "52") (pinfunction "GND_52") (pintype "bidirectional"))
      (node (ref "U$1") (pin "53") (pinfunction "GND_53") (pintype "bidirectional"))
      (node (ref "U$1") (pin "6") (pinfunction "GND_6") (pintype "bidirectional"))
      (node (ref "U$1") (pin "8") (pinfunction "GND_8") (pintype "bidirectional"))
      (node (ref "U$1") (pin "9") (pinfunction "GND_9") (pintype "bidirectional"))
      (node (ref "U$2") (pin "10") (pinfunction "GND_10") (pintype "bidirectional"))
      (node (ref "U$2") (pin "4") (pinfunction "GND_4") (pintype "bidirectional"))
      (node (ref "U$2") (pin "47") (pinfunction "GND_47") (pintype "bidirectional"))
      (node (ref "U$2") (pin "48") (pinfunction "GND_48") (pintype "bidirectional"))
      (node (ref "U$2") (pin "49") (pinfunction "GND_49") (pintype "bidirectional"))
      (node (ref "U$2") (pin "5") (pinfunction "GND_5") (pintype "bidirectional"))
      (node (ref "U$2") (pin "51") (pinfunction "GND_51") (pintype "bidirectional"))
      (node (ref "U$2") (pin "52") (pinfunction "GND_52") (pintype "bidirectional"))
      (node (ref "U$2") (pin "53") (pinfunction "GND_53") (pintype "bidirectional"))
      (node (ref "U$2") (pin "6") (pinfunction "GND_6") (pintype "bidirectional"))
      (node (ref "U$2") (pin "8") (pinfunction "GND_8") (pintype "bidirectional"))
      (node (ref "U$2") (pin "9") (pinfunction "GND_9") (pintype "bidirectional"))
      (node (ref "U$3") (pin "10") (pinfunction "GND_10") (pintype "bidirectional"))
      (node (ref "U$3") (pin "4") (pinfunction "GND_4") (pintype "bidirectional"))
      (node (ref "U$3") (pin "47") (pinfunction "GND_47") (pintype "bidirectional"))
      (node (ref "U$3") (pin "48") (pinfunction "GND_48") (pintype "bidirectional"))
      (node (ref "U$3") (pin "49") (pinfunction "GND_49") (pintype "bidirectional"))
      (node (ref "U$3") (pin "5") (pinfunction "GND_5") (pintype "bidirectional"))
      (node (ref "U$3") (pin "51") (pinfunction "GND_51") (pintype "bidirectional"))
      (node (ref "U$3") (pin "52") (pinfunction "GND_52") (pintype "bidirectional"))
      (node (ref "U$3") (pin "53") (pinfunction "GND_53") (pintype "bidirectional"))
      (node (ref "U$3") (pin "6") (pinfunction "GND_6") (pintype "bidirectional"))
      (node (ref "U$3") (pin "8") (pinfunction "GND_8") (pintype "bidirectional"))
      (node (ref "U$3") (pin "9") (pinfunction "GND_9") (pintype "bidirectional"))
      (node (ref "U$8") (pin "P$8") (pinfunction "GND_P$8") (pintype "bidirectional"))
      (node (ref "U1") (pin "14") (pinfunction "AGND_14") (pintype "power_in"))
      (node (ref "U1") (pin "16") (pinfunction "AGND_16") (pintype "power_in"))
      (node (ref "U1") (pin "19") (pinfunction "AGND_19") (pintype "power_in"))
      (node (ref "U1") (pin "23") (pinfunction "RSVD1_23") (pintype "input"))
      (node (ref "U1") (pin "29") (pinfunction "GND_29") (pintype "passive"))
      (node (ref "U1") (pin "3") (pinfunction "AGND_3") (pintype "power_in"))
      (node (ref "U1") (pin "48") (pinfunction "AGND_48") (pintype "power_in"))
      (node (ref "U1") (pin "9") (pinfunction "AGND_9") (pintype "power_in"))
      (node (ref "U2") (pin "12") (pinfunction "VSSA_12") (pintype "power_in"))
      (node (ref "U2") (pin "18") (pinfunction "VSS_18") (pintype "power_in"))
      (node (ref "U2") (pin "63") (pinfunction "VSS_63") (pintype "power_in"))
    )
    (net (code "13") (name "JETSON_ON{slash}OFF") (class "Default")
      (node (ref "PWR_ON") (pin "P$5") (pinfunction "JETSON_ON/OFF_P$5") (pintype "bidirectional"))
      (node (ref "U$1") (pin "18") (pinfunction "JETSON_ON/OFF_18") (pintype "bidirectional"))
      (node (ref "U$2") (pin "18") (pinfunction "JETSON_ON/OFF_18") (pintype "bidirectional"))
      (node (ref "U$3") (pin "18") (pinfunction "JETSON_ON/OFF_18") (pintype "bidirectional"))
      (node (ref "U2") (pin "11") (pinfunction "PC3/SPI2_MOSI_11") (pintype "bidirectional"))
    )
    (net (code "14") (name "KILL_SWITCH") (class "Default")
      (node (ref "R9") (pin "2") (pinfunction "2_2") (pintype "passive"))
      (node (ref "SWITCH_CONN") (pin "P$7") (pinfunction "KILL_SWITCH_P$7") (pintype "bidirectional"))
      (node (ref "SWITCH_CONNECTOR") (pin "4") (pinfunction "P_4") (pintype "passive"))
      (node (ref "U$1") (pin "37") (pinfunction "KILL_SWITCH_37") (pintype "output"))
      (node (ref "U$2") (pin "37") (pinfunction "KILL_SWITCH_37") (pintype "output"))
      (node (ref "U$3") (pin "37") (pinfunction "KILL_SWITCH_37") (pintype "output"))
      (node (ref "U2") (pin "33") (pinfunction "PB12_33") (pintype "bidirectional"))
    )
    (net (code "15") (name "LED_CYAN2") (class "Default")
      (node (ref "U2") (pin "41") (pinfunction "PA8_41") (pintype "bidirectional"))
    )
    (net (code "16") (name "MOBO_ON{slash}OFF") (class "Default")
      (node (ref "PWR_ON") (pin "P$6") (pinfunction "MOBO_ON/OFF_P$6") (pintype "bidirectional"))
      (node (ref "U$1") (pin "19") (pinfunction "MOBO_ON/OFF_19") (pintype "bidirectional"))
      (node (ref "U$2") (pin "19") (pinfunction "MOBO_ON/OFF_19") (pintype "bidirectional"))
      (node (ref "U$3") (pin "19") (pinfunction "MOBO_ON/OFF_19") (pintype "bidirectional"))
      (node (ref "U2") (pin "10") (pinfunction "PC2/SPI2_MISO_10") (pintype "bidirectional"))
    )
    (net (code "17") (name "NET_INTERRUPT") (class "Default")
      (node (ref "U1") (pin "36") (pinfunction "~{INTN}_36") (pintype "input"))
    )
    (net (code "18") (name "NET_RESET") (class "Default")
      (node (ref "U1") (pin "37") (pinfunction "~{RSTN}_37") (pintype "input"))
      (node (ref "U2") (pin "25") (pinfunction "PC5_25") (pintype "bidirectional"))
    )
    (net (code "19") (name "Net-(C25-Pad2)") (class "Default")
      (node (ref "C25") (pin "2") (pinfunction "2_2") (pintype "passive"))
      (node (ref "R5") (pin "2") (pinfunction "2_2") (pintype "passive"))
      (node (ref "R6") (pin "2") (pinfunction "2_2") (pintype "passive"))
    )
    (net (code "20") (name "Net-(D5-PadC)") (class "Default")
      (node (ref "D5") (pin "C") (pinfunction "C_C") (pintype "passive"))
      (node (ref "R20") (pin "1") (pinfunction "1_1") (pintype "passive"))
    )
    (net (code "21") (name "Net-(P2-PadL1)") (class "Default")
      (node (ref "P2") (pin "L1") (pinfunction "L1_L1") (pintype "passive"))
      (node (ref "R23") (pin "1") (pinfunction "1_1") (pintype "passive"))
    )
    (net (code "22") (name "Net-(P2-PadL3)") (class "Default")
      (node (ref "P2") (pin "L3") (pinfunction "L3_L3") (pintype "passive"))
      (node (ref "R1") (pin "1") (pinfunction "1_1") (pintype "passive"))
    )
    (net (code "23") (name "Net-(P2-RD+)") (class "Default")
      (node (ref "C26") (pin "2") (pinfunction "2_2") (pintype "passive"))
      (node (ref "P2") (pin "R7") (pinfunction "RD+_R7") (pintype "input"))
    )
    (net (code "24") (name "Net-(P2-RD-)") (class "Default")
      (node (ref "C27") (pin "1") (pinfunction "1_1") (pintype "passive"))
      (node (ref "P2") (pin "R8") (pinfunction "RD-_R8") (pintype "input"))
    )
    (net (code "25") (name "Net-(P2-TD+)") (class "Default")
      (node (ref "P2") (pin "R1") (pinfunction "TD+_R1") (pintype "input"))
      (node (ref "R3") (pin "2") (pinfunction "2_2") (pintype "passive"))
      (node (ref "U1") (pin "2") (pinfunction "TXP_2") (pintype "output"))
    )
    (net (code "26") (name "Net-(P2-TD-)") (class "Default")
      (node (ref "P2") (pin "R2") (pinfunction "TD-_R2") (pintype "input"))
      (node (ref "R2") (pin "2") (pinfunction "2_2") (pintype "passive"))
      (node (ref "U1") (pin "1") (pinfunction "TXN_1") (pintype "output"))
    )
    (net (code "27") (name "Net-(S1-2)") (class "Default")
      (node (ref "C23") (pin "2") (pinfunction "2_2") (pintype "passive"))
      (node (ref "C24") (pin "2") (pinfunction "2_2") (pintype "passive"))
      (node (ref "R27") (pin "1") (pinfunction "1_1") (pintype "passive"))
      (node (ref "S1") (pin "3") (pinfunction "2_3") (pintype "passive"))
      (node (ref "U2") (pin "7") (pinfunction "NRST_7") (pintype "bidirectional"))
    )
    (net (code "28") (name "Net-(U1-1V2O)") (class "Default")
      (node (ref "C14") (pin "1") (pinfunction "1_1") (pintype "passive"))
      (node (ref "U1") (pin "22") (pinfunction "1V2O_22") (pintype "output"))
    )
    (net (code "29") (name "Net-(U1-ACTLED)") (class "Default")
      (node (ref "P2") (pin "L2") (pinfunction "L2_L2") (pintype "passive"))
      (node (ref "U1") (pin "27") (pinfunction "ACTLED_27") (pintype "output"))
    )
    (net (code "30") (name "Net-(U1-EXRES1)") (class "Default")
      (node (ref "R19") (pin "2") (pinfunction "2_2") (pintype "passive"))
      (node (ref "U1") (pin "10") (pinfunction "EXRES1_10") (pintype "bidirectional"))
    )
    (net (code "31") (name "Net-(U1-LINKLED)") (class "Default")
      (node (ref "P2") (pin "L4") (pinfunction "L4_L4") (pintype "passive"))
      (node (ref "U1") (pin "25") (pinfunction "LINKLED_25") (pintype "output"))
    )
    (net (code "32") (name "Net-(U1-RXN)") (class "Default")
      (node (ref "C27") (pin "2") (pinfunction "2_2") (pintype "passive"))
      (node (ref "R6") (pin "1") (pinfunction "1_1") (pintype "passive"))
      (node (ref "U1") (pin "5") (pinfunction "RXN_5") (pintype "input"))
    )
    (net (code "33") (name "Net-(U1-RXP)") (class "Default")
      (node (ref "C26") (pin "1") (pinfunction "1_1") (pintype "passive"))
      (node (ref "R5") (pin "1") (pinfunction "1_1") (pintype "passive"))
      (node (ref "U1") (pin "6") (pinfunction "RXP_6") (pintype "input"))
    )
    (net (code "34") (name "Net-(U1-TOCAP)") (class "Default")
      (node (ref "C13") (pin "1") (pinfunction "1_1") (pintype "passive"))
      (node (ref "U1") (pin "20") (pinfunction "TOCAP_20") (pintype "output"))
    )
    (net (code "35") (name "Net-(U1-XI)") (class "Default")
      (node (ref "C15") (pin "1") (pinfunction "1_1") (pintype "passive"))
      (node (ref "R22") (pin "1") (pinfunction "1_1") (pintype "passive"))
      (node (ref "U1") (pin "30") (pinfunction "XI_30") (pintype "input"))
      (node (ref "Y1") (pin "2") (pinfunction "2_2") (pintype "passive"))
    )
    (net (code "36") (name "Net-(U1-XO)") (class "Default")
      (node (ref "C16") (pin "1") (pinfunction "1_1") (pintype "passive"))
      (node (ref "R22") (pin "2") (pinfunction "2_2") (pintype "passive"))
      (node (ref "U1") (pin "31") (pinfunction "XO_31") (pintype "output"))
      (node (ref "Y1") (pin "1") (pinfunction "1_1") (pintype "passive"))
    )
    (net (code "37") (name "Net-(U2-BOOT0)") (class "Default")
      (node (ref "R30") (pin "1") (pinfunction "1_1") (pintype "passive"))
      (node (ref "U2") (pin "60") (pinfunction "BOOT0_60") (pintype "bidirectional"))
    )
    (net (code "38") (name "Net-(U2-PC14{slash}OSC32_IN)") (class "Default")
      (node (ref "C22") (pin "1") (pinfunction "1_1") (pintype "passive"))
      (node (ref "U2") (pin "3") (pinfunction "PC14/OSC32_IN_3") (pintype "bidirectional"))
      (node (ref "Y3") (pin "P$2") (pinfunction "2_P$2") (pintype "passive"))
    )
    (net (code "39") (name "Net-(U2-PC15{slash}OSC32_OUT)") (class "Default")
      (node (ref "C21") (pin "1") (pinfunction "1_1") (pintype "passive"))
      (node (ref "U2") (pin "4") (pinfunction "PC15/OSC32_OUT_4") (pintype "bidirectional"))
      (node (ref "Y3") (pin "P$1") (pinfunction "1_P$1") (pintype "passive"))
    )
    (net (code "40") (name "Net-(U2-PH0{slash}OSC_IN)") (class "Default")
      (node (ref "C18") (pin "1") (pinfunction "1_1") (pintype "passive"))
      (node (ref "U2") (pin "5") (pinfunction "PH0/OSC_IN_5") (pintype "bidirectional"))
      (node (ref "Y2") (pin "2") (pinfunction "2_2") (pintype "passive"))
    )
    (net (code "41") (name "Net-(U2-PH1{slash}OSC_OUT)") (class "Default")
      (node (ref "C17") (pin "1") (pinfunction "1_1") (pintype "passive"))
      (node (ref "U2") (pin "6") (pinfunction "PH1/OSC_OUT_6") (pintype "bidirectional"))
      (node (ref "Y2") (pin "1") (pinfunction "1_1") (pintype "passive"))
    )
    (net (code "42") (name "Net-(U2-VCAP_1)") (class "Default")
      (node (ref "C19") (pin "2") (pinfunction "2_2") (pintype "passive"))
      (node (ref "U2") (pin "31") (pinfunction "VCAP_1_31") (pintype "power_in"))
    )
    (net (code "43") (name "Net-(U2-VCAP_2)") (class "Default")
      (node (ref "C20") (pin "2") (pinfunction "2_2") (pintype "passive"))
      (node (ref "U2") (pin "47") (pinfunction "VCAP_2_47") (pintype "power_in"))
    )
    (net (code "44") (name "PLTA_ON{slash}OFF") (class "Default")
      (node (ref "PWR_ON") (pin "P$8") (pinfunction "SPARE8_P$8") (pintype "bidirectional"))
      (node (ref "SWITCH_CONNECTOR") (pin "1") (pinfunction "P_1") (pintype "passive"))
      (node (ref "U$1") (pin "50") (pinfunction "PLTA_ON/OFF_50") (pintype "bidirectional"))
      (node (ref "U$2") (pin "50") (pinfunction "PLTA_ON/OFF_50") (pintype "bidirectional"))
      (node (ref "U$3") (pin "50") (pinfunction "PLTA_ON/OFF_50") (pintype "bidirectional"))
    )
    (net (code "45") (name "PWM_1") (class "Default")
      (node (ref "Q1") (pin "3") (pinfunction "D_3") (pintype "bidirectional"))
      (node (ref "R26") (pin "2") (pinfunction "2_2") (pintype "passive"))
      (node (ref "U$1") (pin "20") (pinfunction "PWM_1_20") (pintype "bidirectional"))
      (node (ref "U$2") (pin "20") (pinfunction "PWM_1_20") (pintype "bidirectional"))
      (node (ref "U$3") (pin "20") (pinfunction "PWM_1_20") (pintype "bidirectional"))
      (node (ref "U$6") (pin "P$9") (pinfunction "PWM_1_P$9") (pintype "bidirectional"))
    )
    (net (code "46") (name "PWM_2") (class "Default")
      (node (ref "Q5") (pin "3") (pinfunction "D_3") (pintype "bidirectional"))
      (node (ref "R36") (pin "2") (pinfunction "2_2") (pintype "passive"))
      (node (ref "U$1") (pin "21") (pinfunction "PWM_2_21") (pintype "bidirectional"))
      (node (ref "U$2") (pin "21") (pinfunction "PWM_2_21") (pintype "bidirectional"))
      (node (ref "U$3") (pin "21") (pinfunction "PWM_2_21") (pintype "bidirectional"))
      (node (ref "U$6") (pin "P$8") (pinfunction "PWM_2_P$8") (pintype "bidirectional"))
    )
    (net (code "47") (name "PWM_3") (class "Default")
      (node (ref "Q2") (pin "3") (pinfunction "D_3") (pintype "bidirectional"))
      (node (ref "R29") (pin "2") (pinfunction "2_2") (pintype "passive"))
      (node (ref "U$1") (pin "22") (pinfunction "PWM_3_22") (pintype "bidirectional"))
      (node (ref "U$2") (pin "22") (pinfunction "PWM_3_22") (pintype "bidirectional"))
      (node (ref "U$3") (pin "22") (pinfunction "PWM_3_22") (pintype "bidirectional"))
      (node (ref "U$6") (pin "P$7") (pinfunction "PWM_3_P$7") (pintype "bidirectional"))
    )
    (net (code "48") (name "PWM_3V3_1") (class "Default")
      (node (ref "Q1") (pin "2") (pinfunction "S_2") (pintype "bidirectional"))
      (node (ref "R25") (pin "2") (pinfunction "2_2") (pintype "passive"))
      (node (ref "U2") (pin "61") (pinfunction "PB8_61") (pintype "bidirectional"))
    )
    (net (code "49") (name "PWM_3V3_2") (class "Default")
      (node (ref "Q5") (pin "2") (pinfunction "S_2") (pintype "bidirectional"))
      (node (ref "R35") (pin "2") (pinfunction "2_2") (pintype "passive"))
      (node (ref "U2") (pin "62") (pinfunction "PB9_62") (pintype "bidirectional"))
    )
    (net (code "50") (name "PWM_3V3_3") (class "Default")
      (node (ref "Q2") (pin "2") (pinfunction "S_2") (pintype "bidirectional"))
      (node (ref "R28") (pin "2") (pinfunction "2_2") (pintype "passive"))
      (node (ref "U2") (pin "35") (pinfunction "PB14_35") (pintype "bidirectional"))
    )
    (net (code "51") (name "PWM_3V3_4") (class "Default")
      (node (ref "Q6") (pin "2") (pinfunction "S_2") (pintype "bidirectional"))
      (node (ref "R37") (pin "2") (pinfunction "2_2") (pintype "passive"))
      (node (ref "U2") (pin "36") (pinfunction "PB15_36") (pintype "bidirectional"))
    )
    (net (code "52") (name "PWM_3V3_5") (class "Default")
      (node (ref "Q3") (pin "2") (pinfunction "S_2") (pintype "bidirectional"))
      (node (ref "R31") (pin "2") (pinfunction "2_2") (pintype "passive"))
      (node (ref "U2") (pin "14") (pinfunction "PA0/WKUP_14") (pintype "bidirectional"))
    )
    (net (code "53") (name "PWM_3V3_6") (class "Default")
      (node (ref "Q7") (pin "2") (pinfunction "S_2") (pintype "bidirectional"))
      (node (ref "R39") (pin "2") (pinfunction "2_2") (pintype "passive"))
      (node (ref "U2") (pin "15") (pinfunction "PA1/USART2_RTS_15") (pintype "bidirectional"))
    )
    (net (code "54") (name "PWM_3V3_7") (class "Default")
      (node (ref "Q4") (pin "2") (pinfunction "S_2") (pintype "bidirectional"))
      (node (ref "R33") (pin "2") (pinfunction "2_2") (pintype "passive"))
      (node (ref "U2") (pin "16") (pinfunction "PA2/USART2_TX_16") (pintype "bidirectional"))
    )
    (net (code "55") (name "PWM_3V3_8") (class "Default")
      (node (ref "Q8") (pin "2") (pinfunction "S_2") (pintype "bidirectional"))
      (node (ref "R41") (pin "2") (pinfunction "2_2") (pintype "passive"))
      (node (ref "U2") (pin "17") (pinfunction "PA3/USART2_RX_17") (pintype "bidirectional"))
    )
    (net (code "56") (name "PWM_4") (class "Default")
      (node (ref "Q6") (pin "3") (pinfunction "D_3") (pintype "bidirectional"))
      (node (ref "R38") (pin "2") (pinfunction "2_2") (pintype "passive"))
      (node (ref "U$1") (pin "23") (pinfunction "PWM_4_23") (pintype "bidirectional"))
      (node (ref "U$2") (pin "23") (pinfunction "PWM_4_23") (pintype "bidirectional"))
      (node (ref "U$3") (pin "23") (pinfunction "PWM_4_23") (pintype "bidirectional"))
      (node (ref "U$6") (pin "P$6") (pinfunction "PWM_4_P$6") (pintype "bidirectional"))
    )
    (net (code "57") (name "PWM_5") (class "Default")
      (node (ref "Q3") (pin "3") (pinfunction "D_3") (pintype "bidirectional"))
      (node (ref "R32") (pin "2") (pinfunction "2_2") (pintype "passive"))
      (node (ref "U$1") (pin "24") (pinfunction "PWM_5_24") (pintype "bidirectional"))
      (node (ref "U$2") (pin "24") (pinfunction "PWM_5_24") (pintype "bidirectional"))
      (node (ref "U$3") (pin "24") (pinfunction "PWM_5_24") (pintype "bidirectional"))
      (node (ref "U$6") (pin "P$5") (pinfunction "PWM_5_P$5") (pintype "bidirectional"))
    )
    (net (code "58") (name "PWM_6") (class "Default")
      (node (ref "Q7") (pin "3") (pinfunction "D_3") (pintype "bidirectional"))
      (node (ref "R40") (pin "2") (pinfunction "2_2") (pintype "passive"))
      (node (ref "U$1") (pin "25") (pinfunction "PWM_6_25") (pintype "bidirectional"))
      (node (ref "U$2") (pin "25") (pinfunction "PWM_6_25") (pintype "bidirectional"))
      (node (ref "U$3") (pin "25") (pinfunction "PWM_6_25") (pintype "bidirectional"))
      (node (ref "U$6") (pin "P$4") (pinfunction "PWM_6_P$4") (pintype "bidirectional"))
    )
    (net (code "59") (name "PWM_7") (class "Default")
      (node (ref "Q4") (pin "3") (pinfunction "D_3") (pintype "bidirectional"))
      (node (ref "R34") (pin "2") (pinfunction "2_2") (pintype "passive"))
      (node (ref "U$1") (pin "26") (pinfunction "PWM_7_26") (pintype "bidirectional"))
      (node (ref "U$2") (pin "26") (pinfunction "PWM_7_26") (pintype "bidirectional"))
      (node (ref "U$3") (pin "26") (pinfunction "PWM_7_26") (pintype "bidirectional"))
      (node (ref "U$6") (pin "P$3") (pinfunction "PWM_7_P$3") (pintype "bidirectional"))
    )
    (net (code "60") (name "PWM_8") (class "Default")
      (node (ref "Q8") (pin "3") (pinfunction "D_3") (pintype "bidirectional"))
      (node (ref "R42") (pin "2") (pinfunction "2_2") (pintype "passive"))
      (node (ref "U$1") (pin "27") (pinfunction "PWM_8_27") (pintype "bidirectional"))
      (node (ref "U$2") (pin "27") (pinfunction "PWM_8_27") (pintype "bidirectional"))
      (node (ref "U$3") (pin "27") (pinfunction "PWM_8_27") (pintype "bidirectional"))
      (node (ref "U$6") (pin "P$2") (pinfunction "PWM_8_P$2") (pintype "bidirectional"))
    )
    (net (code "61") (name "ROBOT_SCL") (class "Default")
      (node (ref "P3") (pin "4") (pinfunction "P_4") (pintype "passive"))
      (node (ref "R18") (pin "2") (pinfunction "2_2") (pintype "passive"))
      (node (ref "U$1") (pin "29") (pinfunction "ROBOT_SCL_29") (pintype "bidirectional"))
      (node (ref "U$2") (pin "29") (pinfunction "ROBOT_SCL_29") (pintype "bidirectional"))
      (node (ref "U$3") (pin "29") (pinfunction "ROBOT_SCL_29") (pintype "bidirectional"))
      (node (ref "U$8") (pin "P$6") (pinfunction "ROBOT_SCL_P$6") (pintype "bidirectional"))
      (node (ref "U2") (pin "29") (pinfunction "PB10_29") (pintype "bidirectional"))
    )
    (net (code "62") (name "ROBOT_SDA") (class "Default")
      (node (ref "P3") (pin "2") (pinfunction "P_2") (pintype "passive"))
      (node (ref "R17") (pin "2") (pinfunction "2_2") (pintype "passive"))
      (node (ref "U$1") (pin "30") (pinfunction "ROBOT_SDA_30") (pintype "bidirectional"))
      (node (ref "U$2") (pin "30") (pinfunction "ROBOT_SDA_30") (pintype "bidirectional"))
      (node (ref "U$3") (pin "30") (pinfunction "ROBOT_SDA_30") (pintype "bidirectional"))
      (node (ref "U$8") (pin "P$5") (pinfunction "ROBOT_SDA_P$5") (pintype "bidirectional"))
      (node (ref "U2") (pin "30") (pinfunction "PB11_30") (pintype "bidirectional"))
    )
    (net (code "63") (name "SPARE2") (class "Default")
      (node (ref "U$1") (pin "28") (pinfunction "SPARE2_28") (pintype "bidirectional"))
      (node (ref "U$2") (pin "28") (pinfunction "SPARE2_28") (pintype "bidirectional"))
      (node (ref "U$3") (pin "28") (pinfunction "SPARE2_28") (pintype "bidirectional"))
      (node (ref "U$6") (pin "P$1") (pinfunction "SPARE2_P$1") (pintype "bidirectional"))
    )
    (net (code "64") (name "SPARE3") (class "Default")
      (node (ref "U$1") (pin "33") (pinfunction "SPARE3_33") (pintype "bidirectional"))
      (node (ref "U$2") (pin "33") (pinfunction "SPARE3_33") (pintype "bidirectional"))
      (node (ref "U$3") (pin "33") (pinfunction "SPARE3_33") (pintype "bidirectional"))
      (node (ref "U$8") (pin "P$2") (pinfunction "SPARE3_P$2") (pintype "bidirectional"))
    )
    (net (code "65") (name "SPARE4") (class "Default")
      (node (ref "U$1") (pin "34") (pinfunction "SPARE4_34") (pintype "bidirectional"))
      (node (ref "U$2") (pin "34") (pinfunction "SPARE4_34") (pintype "bidirectional"))
      (node (ref "U$3") (pin "34") (pinfunction "SPARE4_34") (pintype "bidirectional"))
      (node (ref "U$8") (pin "P$1") (pinfunction "SPARE4_P$1") (pintype "bidirectional"))
    )
    (net (code "66") (name "SPARE5") (class "Default")
      (node (ref "SWITCH_CONN") (pin "P$9") (pinfunction "SPARE5_P$9") (pintype "bidirectional"))
      (node (ref "U$1") (pin "35") (pinfunction "SPARE5_35") (pintype "bidirectional"))
      (node (ref "U$2") (pin "35") (pinfunction "SPARE5_35") (pintype "bidirectional"))
      (node (ref "U$3") (pin "35") (pinfunction "SPARE5_35") (pintype "bidirectional"))
    )
    (net (code "67") (name "SPARE6") (class "Default")
      (node (ref "SWITCH_CONN") (pin "P$8") (pinfunction "SPARE6_P$8") (pintype "bidirectional"))
      (node (ref "U$1") (pin "36") (pinfunction "SPARE6_36") (pintype "bidirectional"))
      (node (ref "U$2") (pin "36") (pinfunction "SPARE6_36") (pintype "bidirectional"))
      (node (ref "U$3") (pin "36") (pinfunction "SPARE6_36") (pintype "bidirectional"))
    )
    (net (code "68") (name "SPARE7") (class "Default")
      (node (ref "SWITCH_CONN") (pin "P$1") (pinfunction "SPARE7_P$1") (pintype "bidirectional"))
      (node (ref "U$1") (pin "43") (pinfunction "SPARE7_43") (pintype "bidirectional"))
      (node (ref "U$2") (pin "43") (pinfunction "SPARE7_43") (pintype "bidirectional"))
      (node (ref "U$3") (pin "43") (pinfunction "SPARE7_43") (pintype "bidirectional"))
    )
    (net (code "69") (name "SPI_CLK") (class "Default")
      (node (ref "U1") (pin "33") (pinfunction "SCLK_33") (pintype "input"))
      (node (ref "U2") (pin "21") (pinfunction "PA5/SPI1_SCK_21") (pintype "bidirectional"))
    )
    (net (code "70") (name "SPI_MISO") (class "Default")
      (node (ref "U1") (pin "34") (pinfunction "MISO_34") (pintype "output"))
      (node (ref "U2") (pin "22") (pinfunction "PA6/SPI1_MISO_22") (pintype "bidirectional"))
    )
    (net (code "71") (name "SPI_MOSI") (class "Default")
      (node (ref "U1") (pin "35") (pinfunction "MOSI_35") (pintype "input"))
      (node (ref "U2") (pin "23") (pinfunction "PA7/SPI1_MOSI_23") (pintype "bidirectional"))
    )
    (net (code "72") (name "SPI_SS") (class "Default")
      (node (ref "U1") (pin "32") (pinfunction "~{SCSN}_32") (pintype "input"))
      (node (ref "U2") (pin "20") (pinfunction "PA4/USART2_CK_20") (pintype "bidirectional"))
    )
    (net (code "73") (name "SWCLK") (class "Default")
      (node (ref "SWDIO/SWDCLK/RESET") (pin "9") (pinfunction "9_9") (pintype "passive"))
      (node (ref "U2") (pin "49") (pinfunction "PA14/JTCK-SWCLK_49") (pintype "bidirectional"))
    )
    (net (code "74") (name "SWDIO") (class "Default")
      (node (ref "SWDIO/SWDCLK/RESET") (pin "7") (pinfunction "7_7") (pintype "passive"))
      (node (ref "U2") (pin "46") (pinfunction "PA13/JMS-SWDIO_46") (pintype "bidirectional"))
    )
    (net (code "75") (name "SWITCH_1") (class "Default")
      (node (ref "R10") (pin "2") (pinfunction "2_2") (pintype "passive"))
      (node (ref "SWITCH_CONN") (pin "P$6") (pinfunction "SWITCH_1_P$6") (pintype "bidirectional"))
      (node (ref "SWITCH_CONNECTOR") (pin "3") (pinfunction "P_3") (pintype "passive"))
      (node (ref "U$1") (pin "38") (pinfunction "SWITCH_1_38") (pintype "output"))
      (node (ref "U$2") (pin "38") (pinfunction "SWITCH_1_38") (pintype "output"))
      (node (ref "U$3") (pin "38") (pinfunction "SWITCH_1_38") (pintype "output"))
      (node (ref "U2") (pin "34") (pinfunction "PB13_34") (pintype "bidirectional"))
    )
    (net (code "76") (name "SWITCH_2") (class "Default")
      (node (ref "R11") (pin "2") (pinfunction "2_2") (pintype "passive"))
      (node (ref "SWITCH_CONN") (pin "P$5") (pinfunction "SWITCH_2_P$5") (pintype "bidirectional"))
      (node (ref "SWITCH_CONNECTOR") (pin "2") (pinfunction "P_2") (pintype "passive"))
      (node (ref "U$1") (pin "39") (pinfunction "SWITCH_2_39") (pintype "output"))
      (node (ref "U$2") (pin "39") (pinfunction "SWITCH_2_39") (pintype "output"))
      (node (ref "U$3") (pin "39") (pinfunction "SWITCH_2_39") (pintype "output"))
      (node (ref "U2") (pin "37") (pinfunction "PC6_37") (pintype "bidirectional"))
    )
    (net (code "77") (name "SWITCH_3") (class "Default")
      (node (ref "R12") (pin "2") (pinfunction "2_2") (pintype "passive"))
      (node (ref "SWITCH_CONN") (pin "P$4") (pinfunction "SWITCH_3_P$4") (pintype "bidirectional"))
      (node (ref "SWITCH_CONNECTOR") (pin "6") (pinfunction "P_6") (pintype "passive"))
      (node (ref "U$1") (pin "40") (pinfunction "SWITCH_3_40") (pintype "output"))
      (node (ref "U$2") (pin "40") (pinfunction "SWITCH_3_40") (pintype "output"))
      (node (ref "U$3") (pin "40") (pinfunction "SWITCH_3_40") (pintype "output"))
      (node (ref "U2") (pin "38") (pinfunction "PC7_38") (pintype "bidirectional"))
    )
    (net (code "78") (name "SWITCH_4") (class "Default")
      (node (ref "R13") (pin "2") (pinfunction "2_2") (pintype "passive"))
      (node (ref "SWITCH_CONN") (pin "P$3") (pinfunction "SWITCH_4_P$3") (pintype "bidirectional"))
      (node (ref "SWITCH_CONNECTOR") (pin "7") (pinfunction "P_7") (pintype "passive"))
      (node (ref "U$1") (pin "41") (pinfunction "SWITCH_4_41") (pintype "output"))
      (node (ref "U$2") (pin "41") (pinfunction "SWITCH_4_41") (pintype "output"))
      (node (ref "U$3") (pin "41") (pinfunction "SWITCH_4_41") (pintype "output"))
      (node (ref "U2") (pin "24") (pinfunction "PC4_24") (pintype "bidirectional"))
    )
    (net (code "79") (name "SWITCH_5") (class "Default")
      (node (ref "R14") (pin "2") (pinfunction "2_2") (pintype "passive"))
      (node (ref "SWITCH_CONN") (pin "P$2") (pinfunction "SWITCH_5_P$2") (pintype "bidirectional"))
      (node (ref "SWITCH_CONNECTOR") (pin "8") (pinfunction "P_8") (pintype "passive"))
      (node (ref "U$1") (pin "42") (pinfunction "SWITCH_5_42") (pintype "output"))
      (node (ref "U$2") (pin "42") (pinfunction "SWITCH_5_42") (pintype "output"))
      (node (ref "U$3") (pin "42") (pinfunction "SWITCH_5_42") (pintype "output"))
      (node (ref "U2") (pin "27") (pinfunction "PB1_27") (pintype "bidirectional"))
    )
    (net (code "80") (name "VBAT") (class "Default")
      (node (ref "U2") (pin "1") (pinfunction "VBAT_1") (pintype "power_in"))
    )
    (net (code "81") (name "VBUS") (class "Default")
      (node (ref "D5") (pin "A") (pinfunction "A_A") (pintype "passive"))
      (node (ref "J1") (pin "VBUS") (pinfunction "VBUS_VBUS") (pintype "power_in"))
    )
    (net (code "82") (name "VBUS_3.3") (class "Default")
      (node (ref "R20") (pin "2") (pinfunction "2_2") (pintype "passive"))
      (node (ref "R21") (pin "1") (pinfunction "1_1") (pintype "passive"))
      (node (ref "U2") (pin "42") (pinfunction "PA9_42") (pintype "bidirectional"))
    )
    (net (code "83") (name "unconnected-(J1-PadID)") (class "Default")
      (node (ref "J1") (pin "ID") (pinfunction "ID_ID") (pintype "bidirectional"))
    )
    (net (code "84") (name "unconnected-(P2-PadR4)") (class "Default")
      (node (ref "P2") (pin "R4") (pinfunction "R4_R4") (pintype "input"))
    )
    (net (code "85") (name "unconnected-(P2-PadR5)") (class "Default")
      (node (ref "P2") (pin "R5") (pinfunction "R5_R5") (pintype "input"))
    )
    (net (code "86") (name "unconnected-(P2-PadR6)") (class "Default")
      (node (ref "P2") (pin "R6") (pinfunction "R6_R6") (pintype "input"))
    )
    (net (code "87") (name "unconnected-(SWDIO/SWDCLK/RESET-Pad3)") (class "Default")
      (node (ref "SWDIO/SWDCLK/RESET") (pin "3") (pinfunction "3_3") (pintype "passive"))
    )
    (net (code "88") (name "unconnected-(SWDIO/SWDCLK/RESET-Pad5)") (class "Default")
      (node (ref "SWDIO/SWDCLK/RESET") (pin "5") (pinfunction "5_5") (pintype "passive"))
    )
    (net (code "89") (name "unconnected-(SWDIO/SWDCLK/RESET-Pad11)") (class "Default")
      (node (ref "SWDIO/SWDCLK/RESET") (pin "11") (pinfunction "11_11") (pintype "passive"))
    )
    (net (code "90") (name "unconnected-(SWDIO/SWDCLK/RESET-Pad13)") (class "Default")
      (node (ref "SWDIO/SWDCLK/RESET") (pin "13") (pinfunction "13_13") (pintype "passive"))
    )
    (net (code "91") (name "unconnected-(SWDIO/SWDCLK/RESET-Pad15)") (class "Default")
      (node (ref "SWDIO/SWDCLK/RESET") (pin "15") (pinfunction "15_15") (pintype "passive"))
    )
    (net (code "92") (name "unconnected-(SWDIO/SWDCLK/RESET-Pad17)") (class "Default")
      (node (ref "SWDIO/SWDCLK/RESET") (pin "17") (pinfunction "17_17") (pintype "passive"))
    )
    (net (code "93") (name "unconnected-(SWDIO/SWDCLK/RESET-Pad19)") (class "Default")
      (node (ref "SWDIO/SWDCLK/RESET") (pin "19") (pinfunction "19_19") (pintype "passive"))
    )
    (net (code "94") (name "unconnected-(U1-DNC-Pad7)") (class "Default")
      (node (ref "U1") (pin "7") (pinfunction "DNC_7") (pintype "bidirectional"))
    )
    (net (code "95") (name "unconnected-(U1-DUPLED-Pad26)") (class "Default")
      (node (ref "U1") (pin "26") (pinfunction "DUPLED_26") (pintype "output"))
    )
    (net (code "96") (name "unconnected-(U1-PMODE0-Pad45)") (class "Default")
      (node (ref "U1") (pin "45") (pinfunction "PMODE0_45") (pintype "input"))
    )
    (net (code "97") (name "unconnected-(U1-PMODE1-Pad44)") (class "Default")
      (node (ref "U1") (pin "44") (pinfunction "PMODE1_44") (pintype "input"))
    )
    (net (code "98") (name "unconnected-(U1-PMODE2-Pad43)") (class "Default")
      (node (ref "U1") (pin "43") (pinfunction "PMODE2_43") (pintype "input"))
    )
    (net (code "99") (name "unconnected-(U1-RSVD2-Pad38)") (class "Default")
      (node (ref "U1") (pin "38") (pinfunction "RSVD2_38") (pintype "input"))
    )
    (net (code "100") (name "unconnected-(U1-RSVD3-Pad39)") (class "Default")
      (node (ref "U1") (pin "39") (pinfunction "RSVD3_39") (pintype "input"))
    )
    (net (code "101") (name "unconnected-(U1-RSVD4-Pad40)") (class "Default")
      (node (ref "U1") (pin "40") (pinfunction "RSVD4_40") (pintype "input"))
    )
    (net (code "102") (name "unconnected-(U1-RSVD5-Pad41)") (class "Default")
      (node (ref "U1") (pin "41") (pinfunction "RSVD5_41") (pintype "input"))
    )
    (net (code "103") (name "unconnected-(U1-RSVD6-Pad42)") (class "Default")
      (node (ref "U1") (pin "42") (pinfunction "RSVD6_42") (pintype "input"))
    )
    (net (code "104") (name "unconnected-(U1-SPDLED-Pad24)") (class "Default")
      (node (ref "U1") (pin "24") (pinfunction "SPDLED_24") (pintype "output"))
    )
    (net (code "105") (name "unconnected-(U1-VBG-Pad18)") (class "Default")
      (node (ref "U1") (pin "18") (pinfunction "VBG_18") (pintype "output"))
    )
    (net (code "106") (name "unconnected-(U2-PA10-Pad43)") (class "Default")
      (node (ref "U2") (pin "43") (pinfunction "PA10_43") (pintype "bidirectional"))
    )
    (net (code "107") (name "unconnected-(U2-PA15-Pad50)") (class "Default")
      (node (ref "U2") (pin "50") (pinfunction "PA15_50") (pintype "bidirectional"))
    )
    (net (code "108") (name "unconnected-(U2-PB2{slash}BOOT1-Pad28)") (class "Default")
      (node (ref "U2") (pin "28") (pinfunction "PB2/BOOT1_28") (pintype "bidirectional"))
    )
    (net (code "109") (name "unconnected-(U2-PB3-Pad55)") (class "Default")
      (node (ref "U2") (pin "55") (pinfunction "PB3_55") (pintype "bidirectional"))
    )
    (net (code "110") (name "unconnected-(U2-PB4-Pad56)") (class "Default")
      (node (ref "U2") (pin "56") (pinfunction "PB4_56") (pintype "bidirectional"))
    )
    (net (code "111") (name "unconnected-(U2-PB5-Pad57)") (class "Default")
      (node (ref "U2") (pin "57") (pinfunction "PB5_57") (pintype "bidirectional"))
    )
    (net (code "112") (name "unconnected-(U2-PC8-Pad39)") (class "Default")
      (node (ref "U2") (pin "39") (pinfunction "PC8_39") (pintype "bidirectional"))
    )
    (net (code "113") (name "unconnected-(U2-PC9-Pad40)") (class "Default")
      (node (ref "U2") (pin "40") (pinfunction "PC9_40") (pintype "bidirectional"))
    )
    (net (code "114") (name "unconnected-(U2-PC10-Pad51)") (class "Default")
      (node (ref "U2") (pin "51") (pinfunction "PC10_51") (pintype "bidirectional"))
    )
    (net (code "115") (name "unconnected-(U2-PC11-Pad52)") (class "Default")
      (node (ref "U2") (pin "52") (pinfunction "PC11_52") (pintype "bidirectional"))
    )
    (net (code "116") (name "unconnected-(U2-PC12-Pad53)") (class "Default")
      (node (ref "U2") (pin "53") (pinfunction "PC12_53") (pintype "bidirectional"))
    )
    (net (code "117") (name "unconnected-(U2-PD2-Pad54)") (class "Default")
      (node (ref "U2") (pin "54") (pinfunction "PD2_54") (pintype "bidirectional"))
    )
  )
)
